# pocketbone.net
KiCad netlist of a schematic drawn in EAGLE
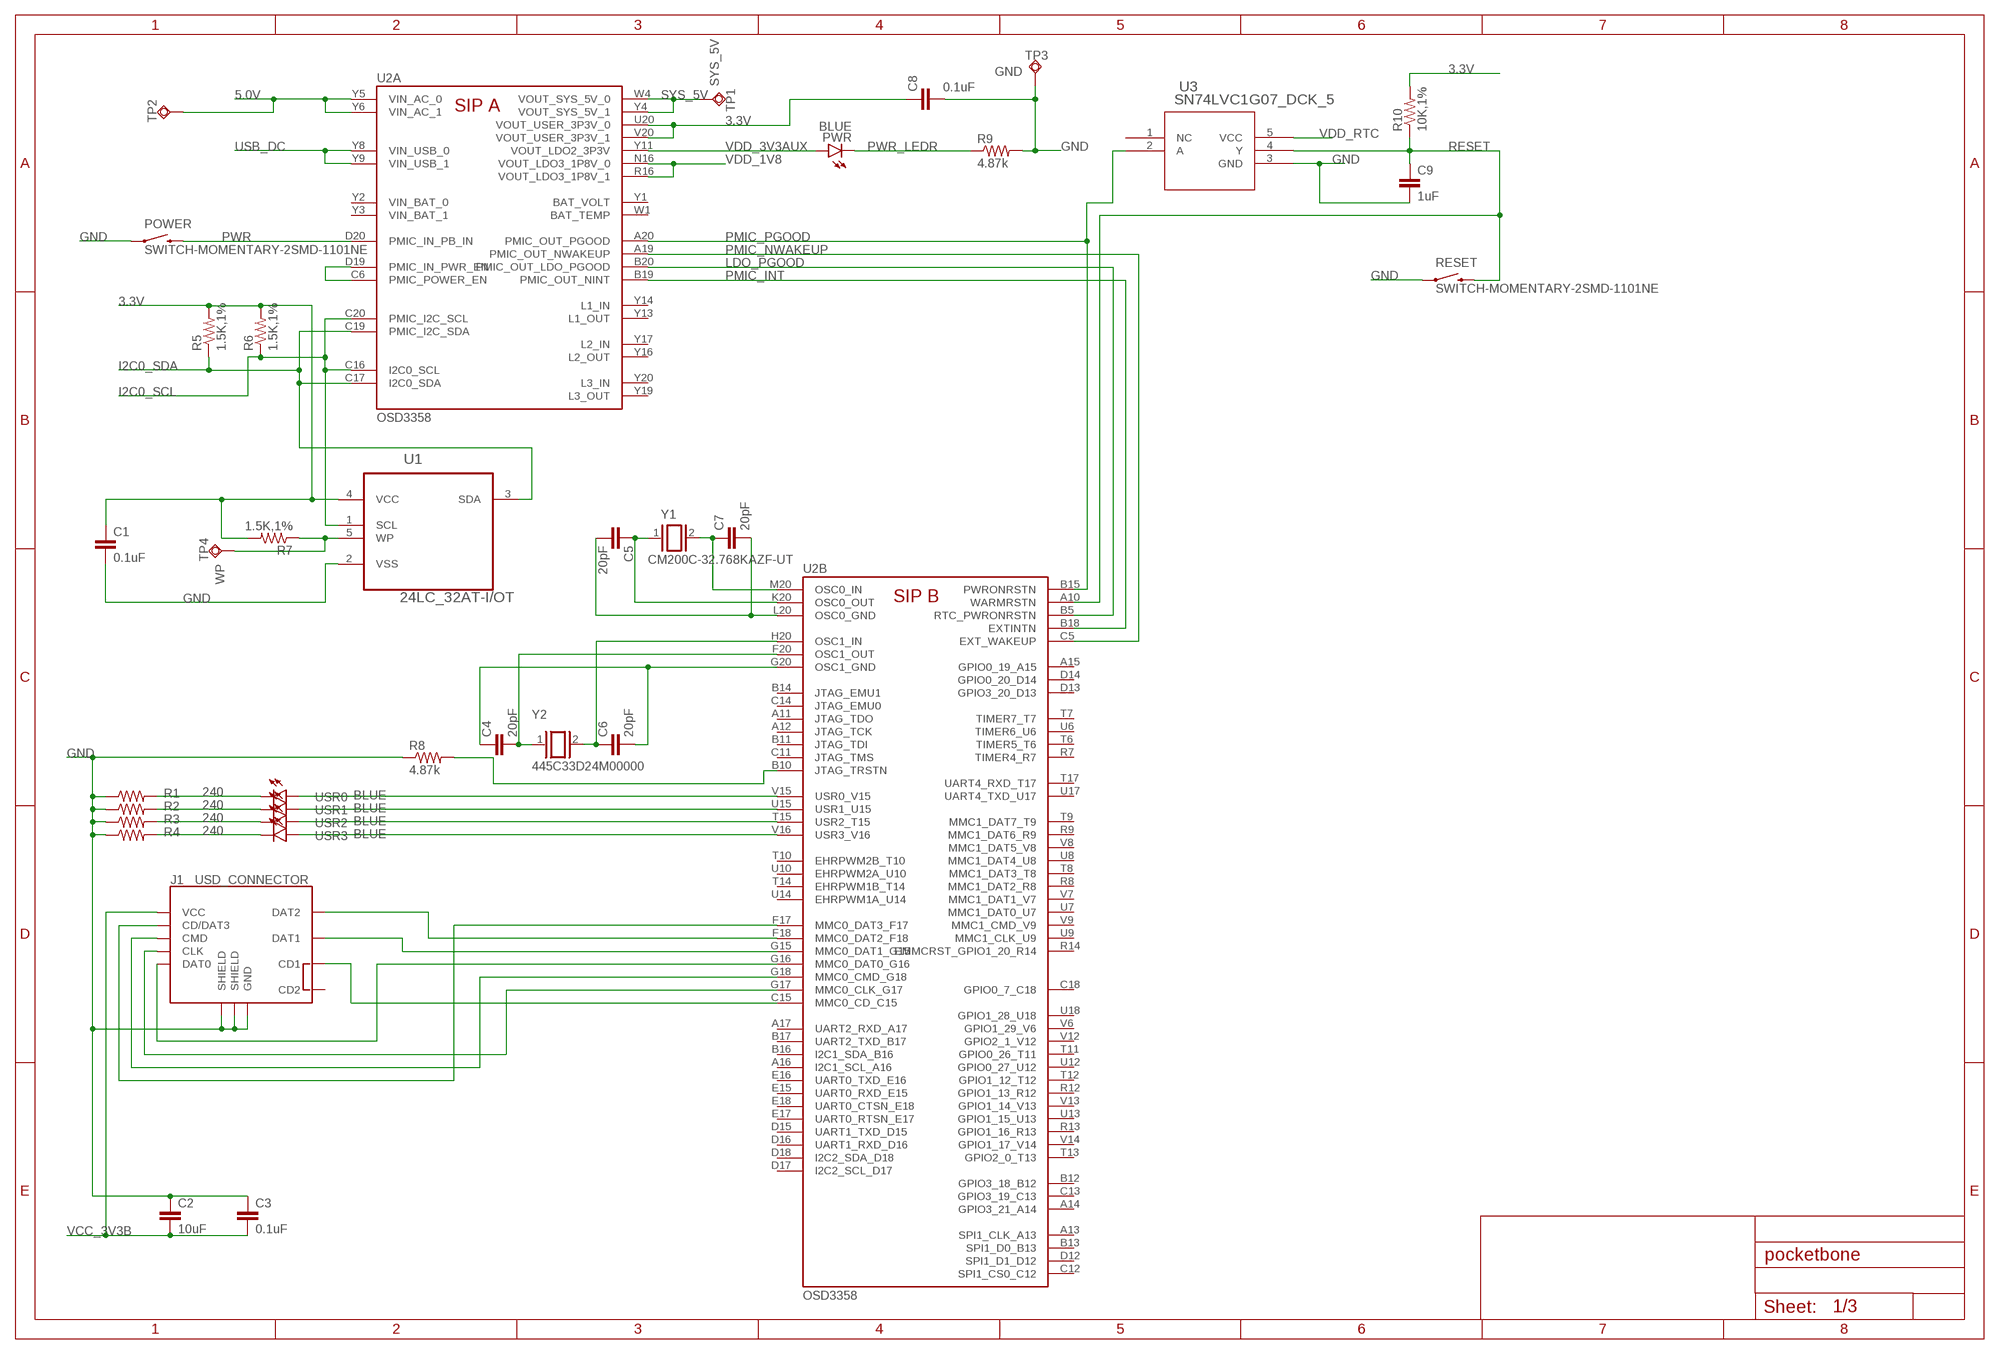
[diagram p0: schematic, sheet 1]
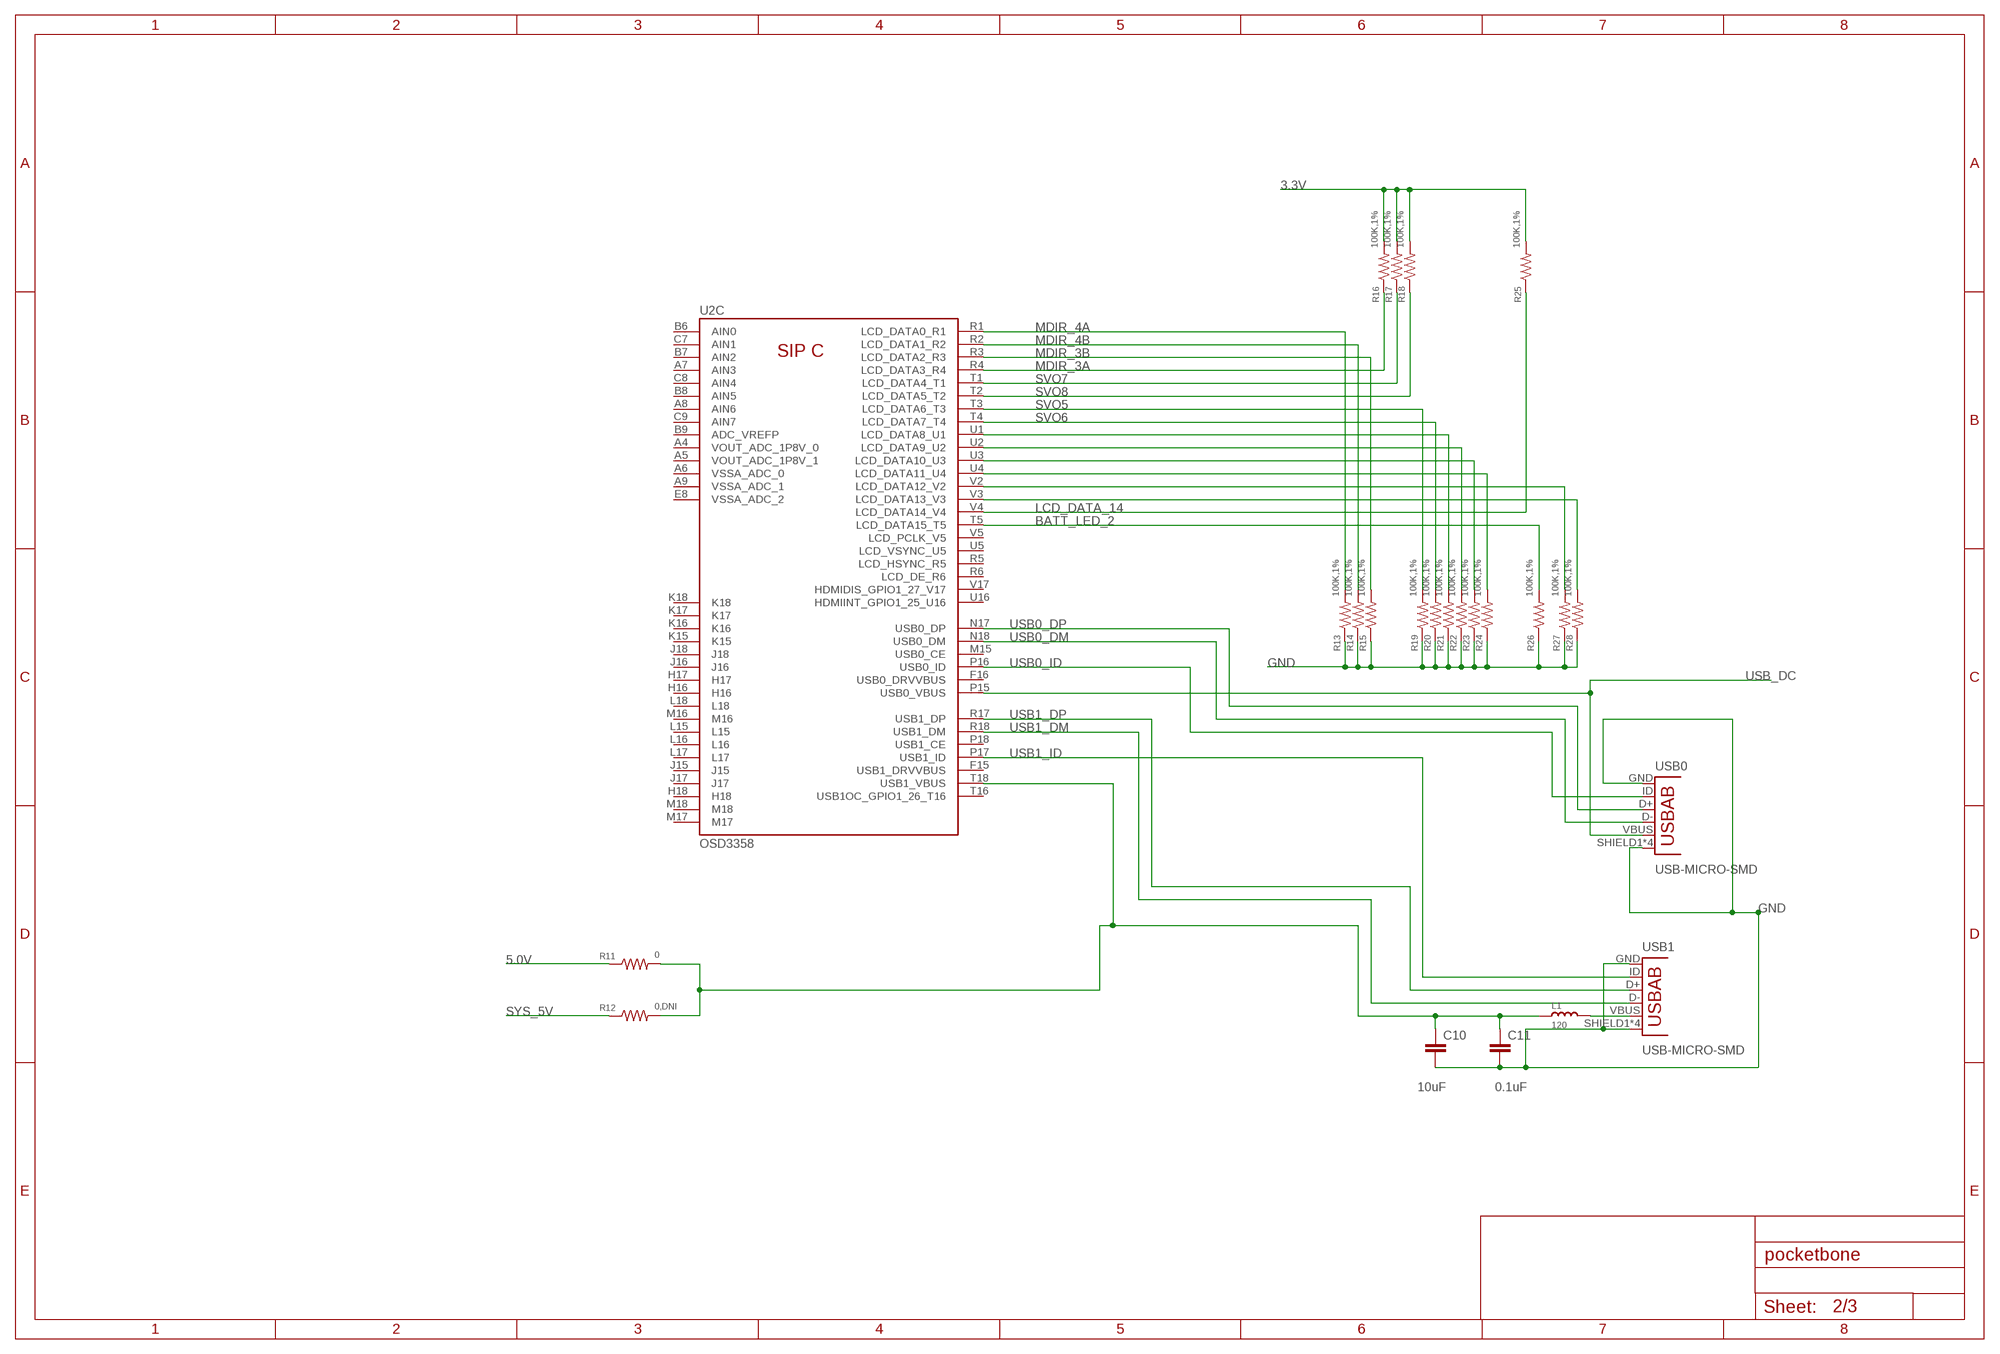
[diagram p1: schematic, sheet 2]
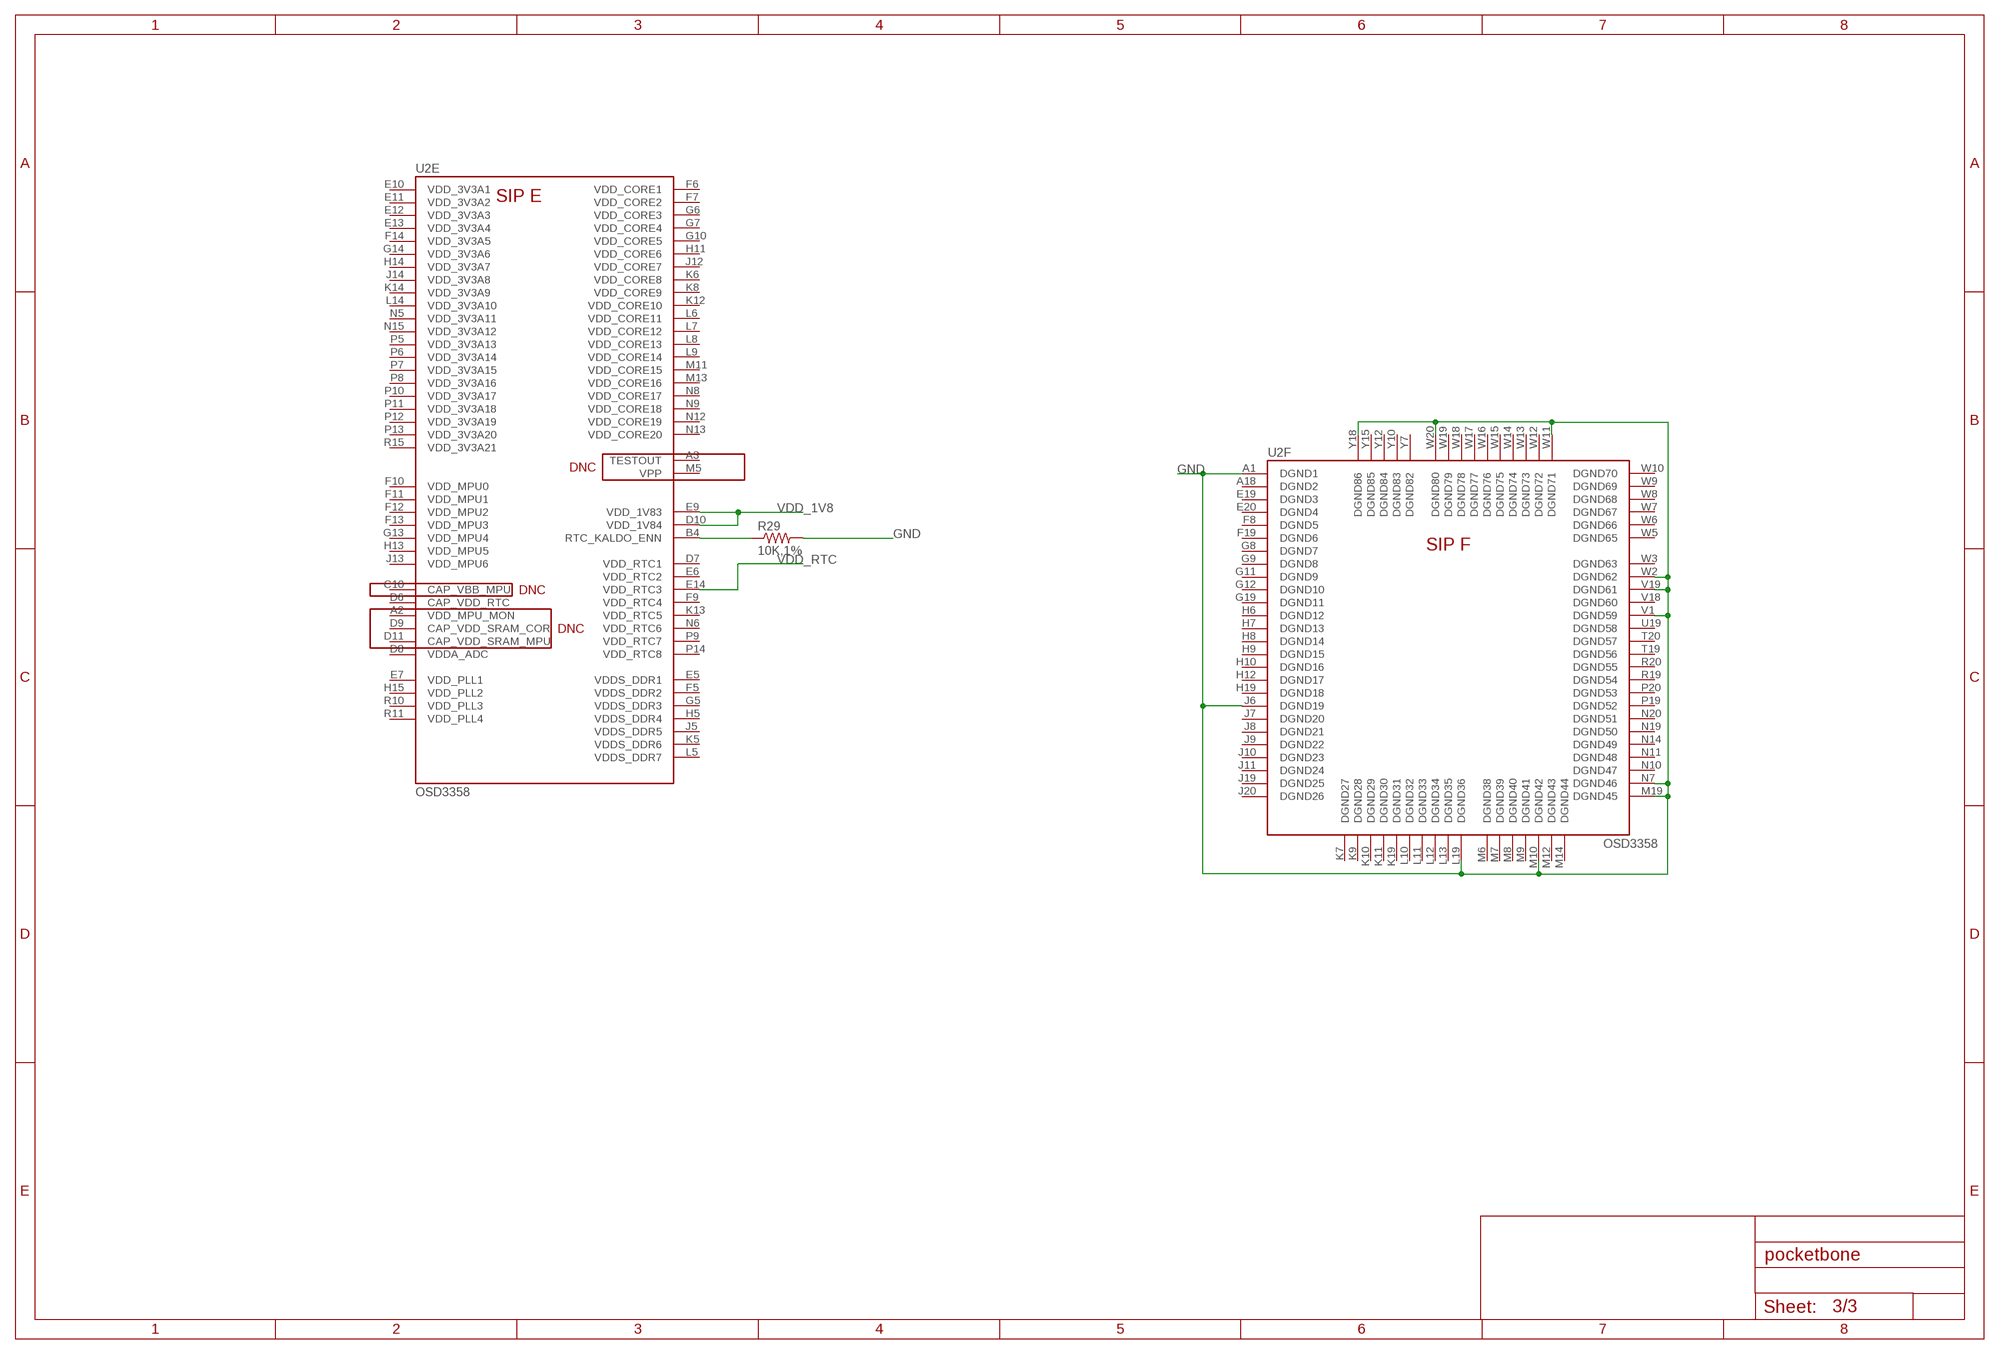
[diagram p2: schematic, sheet 3]

(export (version "E")
  (design (tool "Eeschema 10.0.6"))
  (components
    (comp (ref "C1")
      (value "0.1uF")
      (footprint "eagle-import:0402-CAP")
      (libsource (lib "eagle-import") (part "CAP0402-CAP"))
    )
    (comp (ref "C2")
      (value "10uF")
      (footprint "eagle-import:0805")
      (libsource (lib "eagle-import") (part "CAP0805"))
    )
    (comp (ref "C3")
      (value "0.1uF")
      (footprint "eagle-import:0402-CAP")
      (libsource (lib "eagle-import") (part "CAP0402-CAP"))
    )
    (comp (ref "C4")
      (value "20pF")
      (footprint "eagle-import:0402-CAP")
      (libsource (lib "eagle-import") (part "CAP0402-CAP"))
    )
    (comp (ref "C5")
      (value "20pF")
      (footprint "eagle-import:0402-CAP")
      (libsource (lib "eagle-import") (part "CAP0402-CAP"))
    )
    (comp (ref "C6")
      (value "20pF")
      (footprint "eagle-import:0402-CAP")
      (libsource (lib "eagle-import") (part "CAP0402-CAP"))
    )
    (comp (ref "C7")
      (value "20pF")
      (footprint "eagle-import:0402-CAP")
      (libsource (lib "eagle-import") (part "CAP0402-CAP"))
    )
    (comp (ref "C8")
      (value "0.1uF")
      (footprint "eagle-import:0402-CAP")
      (libsource (lib "eagle-import") (part "CAP0402-CAP"))
    )
    (comp (ref "C9")
      (value "1uF")
      (footprint "eagle-import:0402-CAP")
      (libsource (lib "eagle-import") (part "CAP0402-CAP"))
    )
    (comp (ref "J1")
      (value "USD_CONNECTOR")
      (footprint "eagle-import:MICRO-SD-SOCKET-PP")
      (libsource (lib "eagle-import") (part "USD_CONNECTOR"))
    )
    (comp (ref "POWER")
      (value "SWITCH-MOMENTARY-2SMD-1101NE")
      (footprint "eagle-import:TACTILE-SWITCH-1101NE")
      (libsource (lib "eagle-import") (part "SWITCH-MOMENTARY-2SMD-1101NE"))
    )
    (comp (ref "PWR")
      (value "BLUE")
      (footprint "eagle-import:LED-0603")
      (libsource (lib "eagle-import") (part "LED0603"))
    )
    (comp (ref "R1")
      (value "240")
      (footprint "eagle-import:0402-RES")
      (libsource (lib "eagle-import") (part "RESISTOR0402-RES"))
    )
    (comp (ref "R2")
      (value "240")
      (footprint "eagle-import:0402-RES")
      (libsource (lib "eagle-import") (part "RESISTOR0402-RES"))
    )
    (comp (ref "R3")
      (value "240")
      (footprint "eagle-import:0402-RES")
      (libsource (lib "eagle-import") (part "RESISTOR0402-RES"))
    )
    (comp (ref "R4")
      (value "240")
      (footprint "eagle-import:0402-RES")
      (libsource (lib "eagle-import") (part "RESISTOR0402-RES"))
    )
    (comp (ref "R5")
      (value "1.5K,1%")
      (footprint "eagle-import:0402-RES")
      (libsource (lib "eagle-import") (part "RESISTOR0402-RES"))
    )
    (comp (ref "R6")
      (value "1.5K,1%")
      (footprint "eagle-import:0402-RES")
      (libsource (lib "eagle-import") (part "RESISTOR0402-RES"))
    )
    (comp (ref "R7")
      (value "1.5K,1%")
      (footprint "eagle-import:0402-RES")
      (libsource (lib "eagle-import") (part "RESISTOR0402-RES"))
    )
    (comp (ref "R8")
      (value "4.87k")
      (footprint "eagle-import:0402-RES")
      (libsource (lib "eagle-import") (part "RESISTOR0402-RES"))
    )
    (comp (ref "R9")
      (value "4.87k")
      (footprint "eagle-import:0402-RES")
      (libsource (lib "eagle-import") (part "RESISTOR0402-RES"))
    )
    (comp (ref "R10")
      (value "10K,1%")
      (footprint "eagle-import:0402-RES")
      (libsource (lib "eagle-import") (part "RESISTOR0402-RES"))
    )
    (comp (ref "RESET")
      (value "SWITCH-MOMENTARY-2SMD-1101NE")
      (footprint "eagle-import:TACTILE-SWITCH-1101NE")
      (libsource (lib "eagle-import") (part "SWITCH-MOMENTARY-2SMD-1101NE"))
    )
    (comp (ref "TP1")
      (value "TPSQPAD1-17")
      (footprint "eagle-import:P1-17")
      (fields (field (name "TP_SIGNAL_NAME") "SYS_5V"))
      (libsource (lib "eagle-import") (part "TPSQPAD1-17"))
    )
    (comp (ref "TP2")
      (value "TPSQPAD1-17")
      (footprint "eagle-import:P1-17")
      (fields (field (name "TP_SIGNAL_NAME") "5.0V"))
      (libsource (lib "eagle-import") (part "TPSQPAD1-17"))
    )
    (comp (ref "TP3")
      (value "TPSQPAD1-17")
      (footprint "eagle-import:P1-17")
      (fields (field (name "TP_SIGNAL_NAME") "GND"))
      (libsource (lib "eagle-import") (part "TPSQPAD1-17"))
    )
    (comp (ref "TP4")
      (value "TPSQPAD1-17")
      (footprint "eagle-import:P1-17")
      (fields (field (name "TP_SIGNAL_NAME") "WP"))
      (libsource (lib "eagle-import") (part "TPSQPAD1-17"))
    )
    (comp (ref "U1")
      (value "24LC_32AT-I/OT")
      (footprint "eagle-import:SOT95P290X145-5N")
      (fields (field (name "MPN") "24LC32AT-I/OT"))
      (libsource (lib "eagle-import") (part "24LC_32AT-I/OT"))
    )
    (comp (ref "U2")
      (value "OSD3358")
      (footprint "eagle-import:OSD3358")
      (libsource (lib "eagle-import") (part "OSD3358"))
    )
    (comp (ref "U3")
      (value "SN74LVC1G07_DCK_5")
      (footprint "eagle-import:DCK5")
      (fields
        (field (name "GENERIC_PART_NUMBER") "SN74LVC1G07")
        (field (name "MANUFACTURER") "Texas Instruments")
        (field (name "MANUFACTURER_PART_NUMBER") "sn74lvc1g07_dck_5")
      )
      (libsource (lib "eagle-import") (part "SN74LVC1G07_DCK_5"))
    )
    (comp (ref "USR0")
      (value "BLUE")
      (footprint "eagle-import:LED-0603")
      (libsource (lib "eagle-import") (part "LED0603"))
    )
    (comp (ref "USR1")
      (value "BLUE")
      (footprint "eagle-import:LED-0603")
      (libsource (lib "eagle-import") (part "LED0603"))
    )
    (comp (ref "USR2")
      (value "BLUE")
      (footprint "eagle-import:LED-0603")
      (libsource (lib "eagle-import") (part "LED0603"))
    )
    (comp (ref "USR3")
      (value "BLUE")
      (footprint "eagle-import:LED-0603")
      (libsource (lib "eagle-import") (part "LED0603"))
    )
    (comp (ref "Y1")
      (value "CM200C-32.768KAZF-UT")
      (footprint "eagle-import:CM200C-32.768KAZF-UT")
      (libsource (lib "eagle-import") (part "CM200C-32.768KAZF-UT"))
    )
    (comp (ref "Y2")
      (value "445C33D24M00000")
      (footprint "eagle-import:445C33D24M00000")
      (libsource (lib "eagle-import") (part "445C33D24M00000"))
    )
    (comp (ref "R29")
      (value "10K,1%")
      (footprint "eagle-import:0402-RES")
      (libsource (lib "eagle-import") (part "RESISTOR0402-RES"))
    )
    (comp (ref "C10")
      (value "10uF")
      (footprint "eagle-import:0805")
      (libsource (lib "eagle-import") (part "CAP0805"))
    )
    (comp (ref "C11")
      (value "0.1uF")
      (footprint "eagle-import:0402-CAP")
      (libsource (lib "eagle-import") (part "CAP0402-CAP"))
    )
    (comp (ref "L1")
      (value "120")
      (footprint "eagle-import:L0603")
      (libsource (lib "eagle-import") (part "INDUCTOR/FERRITE-BEAD'0603'"))
    )
    (comp (ref "R11")
      (value "0")
      (footprint "eagle-import:0402-RES")
      (libsource (lib "eagle-import") (part "RESISTOR0402-RES"))
    )
    (comp (ref "R12")
      (value "0,DNI")
      (footprint "eagle-import:0402-RES")
      (libsource (lib "eagle-import") (part "RESISTOR0402-RES"))
    )
    (comp (ref "R13")
      (value "100K,1%")
      (footprint "eagle-import:0402-RES")
      (libsource (lib "eagle-import") (part "RESISTOR0402-RES"))
    )
    (comp (ref "R14")
      (value "100K,1%")
      (footprint "eagle-import:0402-RES")
      (libsource (lib "eagle-import") (part "RESISTOR0402-RES"))
    )
    (comp (ref "R15")
      (value "100K,1%")
      (footprint "eagle-import:0402-RES")
      (libsource (lib "eagle-import") (part "RESISTOR0402-RES"))
    )
    (comp (ref "R16")
      (value "100K,1%")
      (footprint "eagle-import:0402-RES")
      (libsource (lib "eagle-import") (part "RESISTOR0402-RES"))
    )
    (comp (ref "R17")
      (value "100K,1%")
      (footprint "eagle-import:0402-RES")
      (libsource (lib "eagle-import") (part "RESISTOR0402-RES"))
    )
    (comp (ref "R18")
      (value "100K,1%")
      (footprint "eagle-import:0402-RES")
      (libsource (lib "eagle-import") (part "RESISTOR0402-RES"))
    )
    (comp (ref "R19")
      (value "100K,1%")
      (footprint "eagle-import:0402-RES")
      (libsource (lib "eagle-import") (part "RESISTOR0402-RES"))
    )
    (comp (ref "R20")
      (value "100K,1%")
      (footprint "eagle-import:0402-RES")
      (libsource (lib "eagle-import") (part "RESISTOR0402-RES"))
    )
    (comp (ref "R21")
      (value "100K,1%")
      (footprint "eagle-import:0402-RES")
      (libsource (lib "eagle-import") (part "RESISTOR0402-RES"))
    )
    (comp (ref "R22")
      (value "100K,1%")
      (footprint "eagle-import:0402-RES")
      (libsource (lib "eagle-import") (part "RESISTOR0402-RES"))
    )
    (comp (ref "R23")
      (value "100K,1%")
      (footprint "eagle-import:0402-RES")
      (libsource (lib "eagle-import") (part "RESISTOR0402-RES"))
    )
    (comp (ref "R24")
      (value "100K,1%")
      (footprint "eagle-import:0402-RES")
      (libsource (lib "eagle-import") (part "RESISTOR0402-RES"))
    )
    (comp (ref "R25")
      (value "100K,1%")
      (footprint "eagle-import:0402-RES")
      (libsource (lib "eagle-import") (part "RESISTOR0402-RES"))
    )
    (comp (ref "R26")
      (value "100K,1%")
      (footprint "eagle-import:0402-RES")
      (libsource (lib "eagle-import") (part "RESISTOR0402-RES"))
    )
    (comp (ref "R27")
      (value "100K,1%")
      (footprint "eagle-import:0402-RES")
      (libsource (lib "eagle-import") (part "RESISTOR0402-RES"))
    )
    (comp (ref "R28")
      (value "100K,1%")
      (footprint "eagle-import:0402-RES")
      (libsource (lib "eagle-import") (part "RESISTOR0402-RES"))
    )
    (comp (ref "USB0")
      (value "USB-MICRO-SMD")
      (footprint "eagle-import:USB-AB-MICRO-SMD")
      (libsource (lib "eagle-import") (part "USB-AB"))
    )
    (comp (ref "USB1")
      (value "USB-MICRO-SMD")
      (footprint "eagle-import:USB-AB-MICRO-SMD")
      (libsource (lib "eagle-import") (part "USB-AB"))
    )
  )
  (nets
    (net (code "1") (name "3.3V") (class "Default")
      (node (ref "C1") (pin "1") (pinfunction "1_1") (pintype "passive"))
      (node (ref "C8") (pin "1") (pinfunction "1_1") (pintype "passive"))
      (node (ref "R10") (pin "2") (pinfunction "2_2") (pintype "passive"))
      (node (ref "R16") (pin "2") (pinfunction "2_2") (pintype "passive"))
      (node (ref "R17") (pin "2") (pinfunction "2_2") (pintype "passive"))
      (node (ref "R18") (pin "2") (pinfunction "2_2") (pintype "passive"))
      (node (ref "R25") (pin "2") (pinfunction "2_2") (pintype "passive"))
      (node (ref "R5") (pin "2") (pinfunction "2_2") (pintype "passive"))
      (node (ref "R6") (pin "2") (pinfunction "2_2") (pintype "passive"))
      (node (ref "R7") (pin "2") (pinfunction "2_2") (pintype "passive"))
      (node (ref "U1") (pin "4") (pinfunction "VCC_4") (pintype "power_in"))
      (node (ref "U2") (pin "U20") (pinfunction "VOUT_USER_3P3V_0_U20") (pintype "power_in"))
      (node (ref "U2") (pin "V20") (pinfunction "VOUT_USER_3P3V_1_V20") (pintype "power_in"))
    )
    (net (code "2") (name "5.0V") (class "Default")
      (node (ref "R11") (pin "1") (pinfunction "1_1") (pintype "passive"))
      (node (ref "TP2") (pin "TP") (pinfunction "TP_TP") (pintype "input"))
      (node (ref "U2") (pin "Y5") (pinfunction "VIN_AC_0_Y5") (pintype "power_in"))
      (node (ref "U2") (pin "Y6") (pinfunction "VIN_AC_1_Y6") (pintype "power_in"))
    )
    (net (code "3") (name "BATT_LED_2") (class "Default")
      (node (ref "R26") (pin "2") (pinfunction "2_2") (pintype "passive"))
      (node (ref "U2") (pin "T5") (pinfunction "LCD_DATA15_T5_T5") (pintype "bidirectional"))
    )
    (net (code "4") (name "GND") (class "Default")
      (node (ref "C1") (pin "2") (pinfunction "2_2") (pintype "passive"))
      (node (ref "C10") (pin "2") (pinfunction "2_2") (pintype "passive"))
      (node (ref "C11") (pin "2") (pinfunction "2_2") (pintype "passive"))
      (node (ref "C2") (pin "1") (pinfunction "1_1") (pintype "passive"))
      (node (ref "C3") (pin "1") (pinfunction "1_1") (pintype "passive"))
      (node (ref "C8") (pin "2") (pinfunction "2_2") (pintype "passive"))
      (node (ref "C9") (pin "2") (pinfunction "2_2") (pintype "passive"))
      (node (ref "J1") (pin "GND") (pinfunction "GND_GND") (pintype "bidirectional"))
      (node (ref "J1") (pin "GND1") (pinfunction "SHIELD_GND1") (pintype "bidirectional"))
      (node (ref "J1") (pin "GND3") (pinfunction "SHIELD_GND3") (pintype "bidirectional"))
      (node (ref "POWER") (pin "1") (pinfunction "1_1") (pintype "passive"))
      (node (ref "R1") (pin "1") (pinfunction "1_1") (pintype "passive"))
      (node (ref "R13") (pin "1") (pinfunction "1_1") (pintype "passive"))
      (node (ref "R14") (pin "1") (pinfunction "1_1") (pintype "passive"))
      (node (ref "R15") (pin "1") (pinfunction "1_1") (pintype "passive"))
      (node (ref "R19") (pin "1") (pinfunction "1_1") (pintype "passive"))
      (node (ref "R2") (pin "1") (pinfunction "1_1") (pintype "passive"))
      (node (ref "R20") (pin "1") (pinfunction "1_1") (pintype "passive"))
      (node (ref "R21") (pin "1") (pinfunction "1_1") (pintype "passive"))
      (node (ref "R22") (pin "1") (pinfunction "1_1") (pintype "passive"))
      (node (ref "R23") (pin "1") (pinfunction "1_1") (pintype "passive"))
      (node (ref "R24") (pin "1") (pinfunction "1_1") (pintype "passive"))
      (node (ref "R26") (pin "1") (pinfunction "1_1") (pintype "passive"))
      (node (ref "R27") (pin "1") (pinfunction "1_1") (pintype "passive"))
      (node (ref "R28") (pin "1") (pinfunction "1_1") (pintype "passive"))
      (node (ref "R29") (pin "2") (pinfunction "2_2") (pintype "passive"))
      (node (ref "R3") (pin "1") (pinfunction "1_1") (pintype "passive"))
      (node (ref "R4") (pin "1") (pinfunction "1_1") (pintype "passive"))
      (node (ref "R8") (pin "1") (pinfunction "1_1") (pintype "passive"))
      (node (ref "R9") (pin "2") (pinfunction "2_2") (pintype "passive"))
      (node (ref "RESET") (pin "1") (pinfunction "1_1") (pintype "passive"))
      (node (ref "TP3") (pin "TP") (pinfunction "TP_TP") (pintype "input"))
      (node (ref "U1") (pin "2") (pinfunction "VSS_2") (pintype "passive"))
      (node (ref "U2") (pin "A1") (pinfunction "DGND1_A1") (pintype "bidirectional"))
      (node (ref "U2") (pin "J6") (pinfunction "DGND19_J6") (pintype "bidirectional"))
      (node (ref "U2") (pin "L19") (pinfunction "DGND36_L19") (pintype "bidirectional"))
      (node (ref "U2") (pin "M10") (pinfunction "DGND42_M10") (pintype "bidirectional"))
      (node (ref "U2") (pin "M19") (pinfunction "DGND45_M19") (pintype "bidirectional"))
      (node (ref "U2") (pin "N7") (pinfunction "DGND46_N7") (pintype "bidirectional"))
      (node (ref "U2") (pin "V1") (pinfunction "DGND59_V1") (pintype "bidirectional"))
      (node (ref "U2") (pin "V19") (pinfunction "DGND61_V19") (pintype "bidirectional"))
      (node (ref "U2") (pin "W11") (pinfunction "DGND71_W11") (pintype "bidirectional"))
      (node (ref "U2") (pin "W2") (pinfunction "DGND62_W2") (pintype "bidirectional"))
      (node (ref "U2") (pin "W20") (pinfunction "DGND80_W20") (pintype "bidirectional"))
      (node (ref "U2") (pin "Y18") (pinfunction "DGND86_Y18") (pintype "bidirectional"))
      (node (ref "U3") (pin "3") (pinfunction "GND_3") (pintype "power_in"))
      (node (ref "USB0") (pin "GND") (pinfunction "GND_GND") (pintype "bidirectional"))
      (node (ref "USB0") (pin "SHIELD1") (pinfunction "SHIELD_SHIELD1") (pintype "bidirectional"))
      (node (ref "USB0") (pin "SHIELD2") (pinfunction "SHIELD_SHIELD2") (pintype "bidirectional"))
      (node (ref "USB0") (pin "SHIELD3") (pinfunction "SHIELD_SHIELD3") (pintype "bidirectional"))
      (node (ref "USB0") (pin "SHIELD4") (pinfunction "SHIELD_SHIELD4") (pintype "bidirectional"))
      (node (ref "USB1") (pin "GND") (pinfunction "GND_GND") (pintype "bidirectional"))
      (node (ref "USB1") (pin "SHIELD1") (pinfunction "SHIELD_SHIELD1") (pintype "bidirectional"))
      (node (ref "USB1") (pin "SHIELD2") (pinfunction "SHIELD_SHIELD2") (pintype "bidirectional"))
      (node (ref "USB1") (pin "SHIELD3") (pinfunction "SHIELD_SHIELD3") (pintype "bidirectional"))
      (node (ref "USB1") (pin "SHIELD4") (pinfunction "SHIELD_SHIELD4") (pintype "bidirectional"))
    )
    (net (code "5") (name "I2C0_SCL") (class "Default")
      (node (ref "R6") (pin "1") (pinfunction "1_1") (pintype "passive"))
      (node (ref "U1") (pin "1") (pinfunction "SCL_1") (pintype "input"))
      (node (ref "U2") (pin "C16") (pinfunction "I2C0_SCL_C16") (pintype "bidirectional"))
      (node (ref "U2") (pin "C20") (pinfunction "PMIC_I2C_SCL_C20") (pintype "bidirectional"))
    )
    (net (code "6") (name "I2C0_SDA") (class "Default")
      (node (ref "R5") (pin "1") (pinfunction "1_1") (pintype "passive"))
      (node (ref "U1") (pin "3") (pinfunction "SDA_3") (pintype "bidirectional"))
      (node (ref "U2") (pin "C17") (pinfunction "I2C0_SDA_C17") (pintype "bidirectional"))
      (node (ref "U2") (pin "C19") (pinfunction "PMIC_I2C_SDA_C19") (pintype "bidirectional"))
    )
    (net (code "7") (name "LCD_DATA_14") (class "Default")
      (node (ref "R25") (pin "1") (pinfunction "1_1") (pintype "passive"))
      (node (ref "U2") (pin "V4") (pinfunction "LCD_DATA14_V4_V4") (pintype "bidirectional"))
    )
    (net (code "8") (name "LDO_PGOOD") (class "Default")
      (node (ref "U2") (pin "B20") (pinfunction "PMIC_OUT_LDO_PGOOD_B20") (pintype "output"))
      (node (ref "U2") (pin "B5") (pinfunction "RTC_PWRONRSTN_B5") (pintype "bidirectional"))
    )
    (net (code "9") (name "MDIR_3A") (class "Default")
      (node (ref "R16") (pin "1") (pinfunction "1_1") (pintype "passive"))
      (node (ref "U2") (pin "R4") (pinfunction "LCD_DATA3_R4_R4") (pintype "bidirectional"))
    )
    (net (code "10") (name "MDIR_3B") (class "Default")
      (node (ref "R15") (pin "2") (pinfunction "2_2") (pintype "passive"))
      (node (ref "U2") (pin "R3") (pinfunction "LCD_DATA2_R3_R3") (pintype "bidirectional"))
    )
    (net (code "11") (name "MDIR_4A") (class "Default")
      (node (ref "R13") (pin "2") (pinfunction "2_2") (pintype "passive"))
      (node (ref "U2") (pin "R1") (pinfunction "LCD_DATA0_R1_R1") (pintype "bidirectional"))
    )
    (net (code "12") (name "MDIR_4B") (class "Default")
      (node (ref "R14") (pin "2") (pinfunction "2_2") (pintype "passive"))
      (node (ref "U2") (pin "R2") (pinfunction "LCD_DATA1_R2_R2") (pintype "bidirectional"))
    )
    (net (code "13") (name "Net-(L1-Pad2)") (class "Default")
      (node (ref "L1") (pin "2") (pinfunction "2_2") (pintype "passive"))
      (node (ref "USB1") (pin "VBUS") (pinfunction "VBUS_VBUS") (pintype "bidirectional"))
    )
    (net (code "14") (name "Net-(R1-Pad2)") (class "Default")
      (node (ref "R1") (pin "2") (pinfunction "2_2") (pintype "passive"))
      (node (ref "USR0") (pin "C") (pinfunction "C_C") (pintype "passive"))
    )
    (net (code "15") (name "Net-(R2-Pad2)") (class "Default")
      (node (ref "R2") (pin "2") (pinfunction "2_2") (pintype "passive"))
      (node (ref "USR1") (pin "C") (pinfunction "C_C") (pintype "passive"))
    )
    (net (code "16") (name "Net-(R3-Pad2)") (class "Default")
      (node (ref "R3") (pin "2") (pinfunction "2_2") (pintype "passive"))
      (node (ref "USR2") (pin "C") (pinfunction "C_C") (pintype "passive"))
    )
    (net (code "17") (name "Net-(R4-Pad2)") (class "Default")
      (node (ref "R4") (pin "2") (pinfunction "2_2") (pintype "passive"))
      (node (ref "USR3") (pin "C") (pinfunction "C_C") (pintype "passive"))
    )
    (net (code "18") (name "Net-(U1-WP)") (class "Default")
      (node (ref "R7") (pin "1") (pinfunction "1_1") (pintype "passive"))
      (node (ref "TP4") (pin "TP") (pinfunction "TP_TP") (pintype "input"))
      (node (ref "U1") (pin "5") (pinfunction "WP_5") (pintype "input"))
    )
    (net (code "19") (name "Net-(U2A-PMIC_IN_PWR_EN)") (class "Default")
      (node (ref "U2") (pin "C6") (pinfunction "PMIC_POWER_EN_C6") (pintype "output"))
      (node (ref "U2") (pin "D19") (pinfunction "PMIC_IN_PWR_EN_D19") (pintype "input"))
    )
    (net (code "20") (name "Net-(U2B-JTAG_TRSTN)") (class "Default")
      (node (ref "R8") (pin "2") (pinfunction "2_2") (pintype "passive"))
      (node (ref "U2") (pin "B10") (pinfunction "JTAG_TRSTN_B10") (pintype "bidirectional"))
    )
    (net (code "21") (name "Net-(U2B-MMC0_CD_C15)") (class "Default")
      (node (ref "J1") (pin "CD1") (pinfunction "CD1_CD1") (pintype "bidirectional"))
      (node (ref "U2") (pin "C15") (pinfunction "MMC0_CD_C15_C15") (pintype "bidirectional"))
    )
    (net (code "22") (name "Net-(U2B-MMC0_CLK_G17)") (class "Default")
      (node (ref "J1") (pin "CLK") (pinfunction "CLK_CLK") (pintype "bidirectional"))
      (node (ref "U2") (pin "G17") (pinfunction "MMC0_CLK_G17_G17") (pintype "bidirectional"))
    )
    (net (code "23") (name "Net-(U2B-MMC0_CMD_G18)") (class "Default")
      (node (ref "J1") (pin "CMD") (pinfunction "CMD_CMD") (pintype "bidirectional"))
      (node (ref "U2") (pin "G18") (pinfunction "MMC0_CMD_G18_G18") (pintype "bidirectional"))
    )
    (net (code "24") (name "Net-(U2B-MMC0_DAT0_G16)") (class "Default")
      (node (ref "J1") (pin "DAT0") (pinfunction "DAT0_DAT0") (pintype "bidirectional"))
      (node (ref "U2") (pin "G16") (pinfunction "MMC0_DAT0_G16_G16") (pintype "bidirectional"))
    )
    (net (code "25") (name "Net-(U2B-MMC0_DAT1_G15)") (class "Default")
      (node (ref "J1") (pin "DAT1") (pinfunction "DAT1_DAT1") (pintype "bidirectional"))
      (node (ref "U2") (pin "G15") (pinfunction "MMC0_DAT1_G15_G15") (pintype "bidirectional"))
    )
    (net (code "26") (name "Net-(U2B-MMC0_DAT2_F18)") (class "Default")
      (node (ref "J1") (pin "DAT2") (pinfunction "DAT2_DAT2") (pintype "bidirectional"))
      (node (ref "U2") (pin "F18") (pinfunction "MMC0_DAT2_F18_F18") (pintype "bidirectional"))
    )
    (net (code "27") (name "Net-(U2B-MMC0_DAT3_F17)") (class "Default")
      (node (ref "J1") (pin "CD/DAT3") (pinfunction "CD/DAT3_CD/DAT3") (pintype "bidirectional"))
      (node (ref "U2") (pin "F17") (pinfunction "MMC0_DAT3_F17_F17") (pintype "bidirectional"))
    )
    (net (code "28") (name "Net-(U2B-OSC0_GND)") (class "Default")
      (node (ref "C5") (pin "2") (pinfunction "2_2") (pintype "passive"))
      (node (ref "C7") (pin "2") (pinfunction "2_2") (pintype "passive"))
      (node (ref "U2") (pin "L20") (pinfunction "OSC0_GND_L20") (pintype "bidirectional"))
    )
    (net (code "29") (name "Net-(U2B-OSC0_IN)") (class "Default")
      (node (ref "C7") (pin "1") (pinfunction "1_1") (pintype "passive"))
      (node (ref "U2") (pin "M20") (pinfunction "OSC0_IN_M20") (pintype "bidirectional"))
      (node (ref "Y1") (pin "2") (pinfunction "2_2") (pintype "passive"))
    )
    (net (code "30") (name "Net-(U2B-OSC0_OUT)") (class "Default")
      (node (ref "C5") (pin "1") (pinfunction "1_1") (pintype "passive"))
      (node (ref "U2") (pin "K20") (pinfunction "OSC0_OUT_K20") (pintype "bidirectional"))
      (node (ref "Y1") (pin "1") (pinfunction "1_1") (pintype "passive"))
    )
    (net (code "31") (name "Net-(U2B-OSC1_GND)") (class "Default")
      (node (ref "C4") (pin "1") (pinfunction "1_1") (pintype "passive"))
      (node (ref "C6") (pin "2") (pinfunction "2_2") (pintype "passive"))
      (node (ref "U2") (pin "G20") (pinfunction "OSC1_GND_G20") (pintype "bidirectional"))
    )
    (net (code "32") (name "Net-(U2B-OSC1_IN)") (class "Default")
      (node (ref "C6") (pin "1") (pinfunction "1_1") (pintype "passive"))
      (node (ref "U2") (pin "H20") (pinfunction "OSC1_IN_H20") (pintype "bidirectional"))
      (node (ref "Y2") (pin "2") (pinfunction "2_2") (pintype "passive"))
    )
    (net (code "33") (name "Net-(U2B-OSC1_OUT)") (class "Default")
      (node (ref "C4") (pin "2") (pinfunction "2_2") (pintype "passive"))
      (node (ref "U2") (pin "F20") (pinfunction "OSC1_OUT_F20") (pintype "bidirectional"))
      (node (ref "Y2") (pin "1") (pinfunction "1_1") (pintype "passive"))
    )
    (net (code "34") (name "Net-(U2B-USR0_V15)") (class "Default")
      (node (ref "U2") (pin "V15") (pinfunction "USR0_V15_V15") (pintype "bidirectional"))
      (node (ref "USR0") (pin "A") (pinfunction "A_A") (pintype "passive"))
    )
    (net (code "35") (name "Net-(U2B-USR1_U15)") (class "Default")
      (node (ref "U2") (pin "U15") (pinfunction "USR1_U15_U15") (pintype "bidirectional"))
      (node (ref "USR1") (pin "A") (pinfunction "A_A") (pintype "passive"))
    )
    (net (code "36") (name "Net-(U2B-USR2_T15)") (class "Default")
      (node (ref "U2") (pin "T15") (pinfunction "USR2_T15_T15") (pintype "bidirectional"))
      (node (ref "USR2") (pin "A") (pinfunction "A_A") (pintype "passive"))
    )
    (net (code "37") (name "Net-(U2B-USR3_V16)") (class "Default")
      (node (ref "U2") (pin "V16") (pinfunction "USR3_V16_V16") (pintype "bidirectional"))
      (node (ref "USR3") (pin "A") (pinfunction "A_A") (pintype "passive"))
    )
    (net (code "38") (name "Net-(U2C-LCD_DATA8_U1)") (class "Default")
      (node (ref "R21") (pin "2") (pinfunction "2_2") (pintype "passive"))
      (node (ref "U2") (pin "U1") (pinfunction "LCD_DATA8_U1_U1") (pintype "bidirectional"))
    )
    (net (code "39") (name "Net-(U2C-LCD_DATA9_U2)") (class "Default")
      (node (ref "R22") (pin "2") (pinfunction "2_2") (pintype "passive"))
      (node (ref "U2") (pin "U2") (pinfunction "LCD_DATA9_U2_U2") (pintype "bidirectional"))
    )
    (net (code "40") (name "Net-(U2C-LCD_DATA10_U3)") (class "Default")
      (node (ref "R23") (pin "2") (pinfunction "2_2") (pintype "passive"))
      (node (ref "U2") (pin "U3") (pinfunction "LCD_DATA10_U3_U3") (pintype "bidirectional"))
    )
    (net (code "41") (name "Net-(U2C-LCD_DATA11_U4)") (class "Default")
      (node (ref "R24") (pin "2") (pinfunction "2_2") (pintype "passive"))
      (node (ref "U2") (pin "U4") (pinfunction "LCD_DATA11_U4_U4") (pintype "bidirectional"))
    )
    (net (code "42") (name "Net-(U2C-LCD_DATA12_V2)") (class "Default")
      (node (ref "R27") (pin "2") (pinfunction "2_2") (pintype "passive"))
      (node (ref "U2") (pin "V2") (pinfunction "LCD_DATA12_V2_V2") (pintype "bidirectional"))
    )
    (net (code "43") (name "Net-(U2C-LCD_DATA13_V3)") (class "Default")
      (node (ref "R28") (pin "2") (pinfunction "2_2") (pintype "passive"))
      (node (ref "U2") (pin "V3") (pinfunction "LCD_DATA13_V3_V3") (pintype "bidirectional"))
    )
    (net (code "44") (name "Net-(U2C-USB1_VBUS)") (class "Default")
      (node (ref "C10") (pin "1") (pinfunction "1_1") (pintype "passive"))
      (node (ref "C11") (pin "1") (pinfunction "1_1") (pintype "passive"))
      (node (ref "L1") (pin "1") (pinfunction "1_1") (pintype "passive"))
      (node (ref "R11") (pin "2") (pinfunction "2_2") (pintype "passive"))
      (node (ref "R12") (pin "2") (pinfunction "2_2") (pintype "passive"))
      (node (ref "U2") (pin "T18") (pinfunction "USB1_VBUS_T18") (pintype "bidirectional"))
    )
    (net (code "45") (name "Net-(U2E-RTC_KALDO_ENN)") (class "Default")
      (node (ref "R29") (pin "1") (pinfunction "1_1") (pintype "passive"))
      (node (ref "U2") (pin "B4") (pinfunction "RTC_KALDO_ENN_B4") (pintype "bidirectional"))
    )
    (net (code "46") (name "PMIC_INT") (class "Default")
      (node (ref "U2") (pin "B18") (pinfunction "EXTINTN_B18") (pintype "bidirectional"))
      (node (ref "U2") (pin "B19") (pinfunction "PMIC_OUT_NINT_B19") (pintype "output"))
    )
    (net (code "47") (name "PMIC_NWAKEUP") (class "Default")
      (node (ref "U2") (pin "A19") (pinfunction "PMIC_OUT_NWAKEUP_A19") (pintype "output"))
      (node (ref "U2") (pin "C5") (pinfunction "EXT_WAKEUP_C5") (pintype "bidirectional"))
    )
    (net (code "48") (name "PMIC_PGOOD") (class "Default")
      (node (ref "U2") (pin "A20") (pinfunction "PMIC_OUT_PGOOD_A20") (pintype "output"))
      (node (ref "U2") (pin "B15") (pinfunction "PWRONRSTN_B15") (pintype "bidirectional"))
      (node (ref "U3") (pin "2") (pinfunction "A_2") (pintype "input"))
    )
    (net (code "49") (name "PWR") (class "Default")
      (node (ref "POWER") (pin "2") (pinfunction "2_2") (pintype "passive"))
      (node (ref "U2") (pin "D20") (pinfunction "PMIC_IN_PB_IN_D20") (pintype "bidirectional"))
    )
    (net (code "50") (name "PWR_LEDR") (class "Default")
      (node (ref "PWR") (pin "C") (pinfunction "C_C") (pintype "passive"))
      (node (ref "R9") (pin "1") (pinfunction "1_1") (pintype "passive"))
    )
    (net (code "51") (name "RESET") (class "Default")
      (node (ref "C9") (pin "1") (pinfunction "1_1") (pintype "passive"))
      (node (ref "R10") (pin "1") (pinfunction "1_1") (pintype "passive"))
      (node (ref "RESET") (pin "2") (pinfunction "2_2") (pintype "passive"))
      (node (ref "U2") (pin "A10") (pinfunction "WARMRSTN_A10") (pintype "bidirectional"))
      (node (ref "U3") (pin "4") (pinfunction "Y_4") (pintype "output"))
    )
    (net (code "52") (name "SVO5") (class "Default")
      (node (ref "R19") (pin "2") (pinfunction "2_2") (pintype "passive"))
      (node (ref "U2") (pin "T3") (pinfunction "LCD_DATA6_T3_T3") (pintype "bidirectional"))
    )
    (net (code "53") (name "SVO6") (class "Default")
      (node (ref "R20") (pin "2") (pinfunction "2_2") (pintype "passive"))
      (node (ref "U2") (pin "T4") (pinfunction "LCD_DATA7_T4_T4") (pintype "bidirectional"))
    )
    (net (code "54") (name "SVO7") (class "Default")
      (node (ref "R17") (pin "1") (pinfunction "1_1") (pintype "passive"))
      (node (ref "U2") (pin "T1") (pinfunction "LCD_DATA4_T1_T1") (pintype "bidirectional"))
    )
    (net (code "55") (name "SVO8") (class "Default")
      (node (ref "R18") (pin "1") (pinfunction "1_1") (pintype "passive"))
      (node (ref "U2") (pin "T2") (pinfunction "LCD_DATA5_T2_T2") (pintype "bidirectional"))
    )
    (net (code "56") (name "SYS_5V") (class "Default")
      (node (ref "R12") (pin "1") (pinfunction "1_1") (pintype "passive"))
      (node (ref "TP1") (pin "TP") (pinfunction "TP_TP") (pintype "input"))
      (node (ref "U2") (pin "W4") (pinfunction "VOUT_SYS_5V_0_W4") (pintype "power_in"))
      (node (ref "U2") (pin "Y4") (pinfunction "VOUT_SYS_5V_1_Y4") (pintype "power_in"))
    )
    (net (code "57") (name "USB0_DM") (class "Default")
      (node (ref "U2") (pin "N18") (pinfunction "USB0_DM_N18") (pintype "bidirectional"))
      (node (ref "USB0") (pin "D-") (pinfunction "D-_D-") (pintype "bidirectional"))
    )
    (net (code "58") (name "USB0_DP") (class "Default")
      (node (ref "U2") (pin "N17") (pinfunction "USB0_DP_N17") (pintype "bidirectional"))
      (node (ref "USB0") (pin "D+") (pinfunction "D+_D+") (pintype "bidirectional"))
    )
    (net (code "59") (name "USB0_ID") (class "Default")
      (node (ref "U2") (pin "P16") (pinfunction "USB0_ID_P16") (pintype "bidirectional"))
      (node (ref "USB0") (pin "ID") (pinfunction "USBID_ID") (pintype "bidirectional"))
    )
    (net (code "60") (name "USB1_DM") (class "Default")
      (node (ref "U2") (pin "R18") (pinfunction "USB1_DM_R18") (pintype "bidirectional"))
      (node (ref "USB1") (pin "D-") (pinfunction "D-_D-") (pintype "bidirectional"))
    )
    (net (code "61") (name "USB1_DP") (class "Default")
      (node (ref "U2") (pin "R17") (pinfunction "USB1_DP_R17") (pintype "bidirectional"))
      (node (ref "USB1") (pin "D+") (pinfunction "D+_D+") (pintype "bidirectional"))
    )
    (net (code "62") (name "USB1_ID") (class "Default")
      (node (ref "U2") (pin "P17") (pinfunction "USB1_ID_P17") (pintype "bidirectional"))
      (node (ref "USB1") (pin "ID") (pinfunction "USBID_ID") (pintype "bidirectional"))
    )
    (net (code "63") (name "USB_DC") (class "Default")
      (node (ref "U2") (pin "P15") (pinfunction "USB0_VBUS_P15") (pintype "bidirectional"))
      (node (ref "U2") (pin "Y8") (pinfunction "VIN_USB_0_Y8") (pintype "power_in"))
      (node (ref "U2") (pin "Y9") (pinfunction "VIN_USB_1_Y9") (pintype "power_in"))
      (node (ref "USB0") (pin "VBUS") (pinfunction "VBUS_VBUS") (pintype "bidirectional"))
    )
    (net (code "64") (name "VCC_3V3B") (class "Default")
      (node (ref "C2") (pin "2") (pinfunction "2_2") (pintype "passive"))
      (node (ref "C3") (pin "2") (pinfunction "2_2") (pintype "passive"))
      (node (ref "J1") (pin "VCC") (pinfunction "VCC_VCC") (pintype "bidirectional"))
    )
    (net (code "65") (name "VDD_1V8") (class "Default")
      (node (ref "U2") (pin "D10") (pinfunction "VDD_1V84_D10") (pintype "bidirectional"))
      (node (ref "U2") (pin "E9") (pinfunction "VDD_1V83_E9") (pintype "bidirectional"))
      (node (ref "U2") (pin "N16") (pinfunction "VOUT_LDO3_1P8V_0_N16") (pintype "power_in"))
      (node (ref "U2") (pin "R16") (pinfunction "VOUT_LDO3_1P8V_1_R16") (pintype "power_in"))
    )
    (net (code "66") (name "VDD_3V3AUX") (class "Default")
      (node (ref "PWR") (pin "A") (pinfunction "A_A") (pintype "passive"))
      (node (ref "U2") (pin "Y11") (pinfunction "VOUT_LDO2_3P3V_Y11") (pintype "power_in"))
    )
    (net (code "67") (name "VDD_RTC") (class "Default")
      (node (ref "U2") (pin "E14") (pinfunction "VDD_RTC3_E14") (pintype "bidirectional"))
      (node (ref "U3") (pin "5") (pinfunction "VCC_5") (pintype "power_in"))
    )
    (net (code "68") (name "VIN_BAT_0") (class "Default")
      (node (ref "U2") (pin "Y2") (pinfunction "VIN_BAT_0_Y2") (pintype "power_in"))
    )
    (net (code "69") (name "VIN_BAT_1") (class "Default")
      (node (ref "U2") (pin "Y3") (pinfunction "VIN_BAT_1_Y3") (pintype "power_in"))
    )
    (net (code "70") (name "unconnected-(J1-PadCD2)") (class "Default")
      (node (ref "J1") (pin "CD2") (pinfunction "CD2_CD2") (pintype "bidirectional"))
    )
    (net (code "71") (name "unconnected-(U2-PadH16)") (class "Default")
      (node (ref "U2") (pin "H16") (pinfunction "H16_H16") (pintype "bidirectional"))
    )
    (net (code "72") (name "unconnected-(U2-PadH17)") (class "Default")
      (node (ref "U2") (pin "H17") (pinfunction "H17_H17") (pintype "bidirectional"))
    )
    (net (code "73") (name "unconnected-(U2-PadH18)") (class "Default")
      (node (ref "U2") (pin "H18") (pinfunction "H18_H18") (pintype "bidirectional"))
    )
    (net (code "74") (name "unconnected-(U2-PadJ15)") (class "Default")
      (node (ref "U2") (pin "J15") (pinfunction "J15_J15") (pintype "bidirectional"))
    )
    (net (code "75") (name "unconnected-(U2-PadJ16)") (class "Default")
      (node (ref "U2") (pin "J16") (pinfunction "J16_J16") (pintype "bidirectional"))
    )
    (net (code "76") (name "unconnected-(U2-PadJ17)") (class "Default")
      (node (ref "U2") (pin "J17") (pinfunction "J17_J17") (pintype "bidirectional"))
    )
    (net (code "77") (name "unconnected-(U2-PadJ18)") (class "Default")
      (node (ref "U2") (pin "J18") (pinfunction "J18_J18") (pintype "bidirectional"))
    )
    (net (code "78") (name "unconnected-(U2-PadK15)") (class "Default")
      (node (ref "U2") (pin "K15") (pinfunction "K15_K15") (pintype "bidirectional"))
    )
    (net (code "79") (name "unconnected-(U2-PadK16)") (class "Default")
      (node (ref "U2") (pin "K16") (pinfunction "K16_K16") (pintype "bidirectional"))
    )
    (net (code "80") (name "unconnected-(U2-PadK17)") (class "Default")
      (node (ref "U2") (pin "K17") (pinfunction "K17_K17") (pintype "bidirectional"))
    )
    (net (code "81") (name "unconnected-(U2-PadK18)") (class "Default")
      (node (ref "U2") (pin "K18") (pinfunction "K18_K18") (pintype "bidirectional"))
    )
    (net (code "82") (name "unconnected-(U2-PadL15)") (class "Default")
      (node (ref "U2") (pin "L15") (pinfunction "L15_L15") (pintype "bidirectional"))
    )
    (net (code "83") (name "unconnected-(U2-PadL16)") (class "Default")
      (node (ref "U2") (pin "L16") (pinfunction "L16_L16") (pintype "bidirectional"))
    )
    (net (code "84") (name "unconnected-(U2-PadL17)") (class "Default")
      (node (ref "U2") (pin "L17") (pinfunction "L17_L17") (pintype "bidirectional"))
    )
    (net (code "85") (name "unconnected-(U2-PadL18)") (class "Default")
      (node (ref "U2") (pin "L18") (pinfunction "L18_L18") (pintype "bidirectional"))
    )
    (net (code "86") (name "unconnected-(U2-PadM16)") (class "Default")
      (node (ref "U2") (pin "M16") (pinfunction "M16_M16") (pintype "bidirectional"))
    )
    (net (code "87") (name "unconnected-(U2-PadM17)") (class "Default")
      (node (ref "U2") (pin "M17") (pinfunction "M17_M17") (pintype "bidirectional"))
    )
    (net (code "88") (name "unconnected-(U2-PadM18)") (class "Default")
      (node (ref "U2") (pin "M18") (pinfunction "M18_M18") (pintype "bidirectional"))
    )
    (net (code "89") (name "unconnected-(U2A-BAT_TEMP-PadW1)") (class "Default")
      (node (ref "U2") (pin "W1") (pinfunction "BAT_TEMP_W1") (pintype "bidirectional"))
    )
    (net (code "90") (name "unconnected-(U2A-BAT_VOLT-PadY1)") (class "Default")
      (node (ref "U2") (pin "Y1") (pinfunction "BAT_VOLT_Y1") (pintype "bidirectional"))
    )
    (net (code "91") (name "unconnected-(U2A-L1_IN-PadY14)") (class "Default")
      (node (ref "U2") (pin "Y14") (pinfunction "L1_IN_Y14") (pintype "bidirectional"))
    )
    (net (code "92") (name "unconnected-(U2A-L1_OUT-PadY13)") (class "Default")
      (node (ref "U2") (pin "Y13") (pinfunction "L1_OUT_Y13") (pintype "bidirectional"))
    )
    (net (code "93") (name "unconnected-(U2A-L2_IN-PadY17)") (class "Default")
      (node (ref "U2") (pin "Y17") (pinfunction "L2_IN_Y17") (pintype "bidirectional"))
    )
    (net (code "94") (name "unconnected-(U2A-L2_OUT-PadY16)") (class "Default")
      (node (ref "U2") (pin "Y16") (pinfunction "L2_OUT_Y16") (pintype "bidirectional"))
    )
    (net (code "95") (name "unconnected-(U2A-L3_IN-PadY20)") (class "Default")
      (node (ref "U2") (pin "Y20") (pinfunction "L3_IN_Y20") (pintype "bidirectional"))
    )
    (net (code "96") (name "unconnected-(U2A-L3_OUT-PadY19)") (class "Default")
      (node (ref "U2") (pin "Y19") (pinfunction "L3_OUT_Y19") (pintype "bidirectional"))
    )
    (net (code "97") (name "unconnected-(U2B-EHRPWM1A_U14-PadU14)") (class "Default")
      (node (ref "U2") (pin "U14") (pinfunction "EHRPWM1A_U14_U14") (pintype "bidirectional"))
    )
    (net (code "98") (name "unconnected-(U2B-EHRPWM1B_T14-PadT14)") (class "Default")
      (node (ref "U2") (pin "T14") (pinfunction "EHRPWM1B_T14_T14") (pintype "bidirectional"))
    )
    (net (code "99") (name "unconnected-(U2B-EHRPWM2A_U10-PadU10)") (class "Default")
      (node (ref "U2") (pin "U10") (pinfunction "EHRPWM2A_U10_U10") (pintype "bidirectional"))
    )
    (net (code "100") (name "unconnected-(U2B-EHRPWM2B_T10-PadT10)") (class "Default")
      (node (ref "U2") (pin "T10") (pinfunction "EHRPWM2B_T10_T10") (pintype "bidirectional"))
    )
    (net (code "101") (name "unconnected-(U2B-EMMCRST_GPIO1_20_R14-PadR14)") (class "Default")
      (node (ref "U2") (pin "R14") (pinfunction "EMMCRST_GPIO1_20_R14_R14") (pintype "bidirectional"))
    )
    (net (code "102") (name "unconnected-(U2B-GPIO0_7_C18-PadC18)") (class "Default")
      (node (ref "U2") (pin "C18") (pinfunction "GPIO0_7_C18_C18") (pintype "bidirectional"))
    )
    (net (code "103") (name "unconnected-(U2B-GPIO0_19_A15-PadA15)") (class "Default")
      (node (ref "U2") (pin "A15") (pinfunction "GPIO0_19_A15_A15") (pintype "bidirectional"))
    )
    (net (code "104") (name "unconnected-(U2B-GPIO0_20_D14-PadD14)") (class "Default")
      (node (ref "U2") (pin "D14") (pinfunction "GPIO0_20_D14_D14") (pintype "bidirectional"))
    )
    (net (code "105") (name "unconnected-(U2B-GPIO0_26_T11-PadT11)") (class "Default")
      (node (ref "U2") (pin "T11") (pinfunction "GPIO0_26_T11_T11") (pintype "bidirectional"))
    )
    (net (code "106") (name "unconnected-(U2B-GPIO0_27_U12-PadU12)") (class "Default")
      (node (ref "U2") (pin "U12") (pinfunction "GPIO0_27_U12_U12") (pintype "bidirectional"))
    )
    (net (code "107") (name "unconnected-(U2B-GPIO1_12_T12-PadT12)") (class "Default")
      (node (ref "U2") (pin "T12") (pinfunction "GPIO1_12_T12_T12") (pintype "bidirectional"))
    )
    (net (code "108") (name "unconnected-(U2B-GPIO1_13_R12-PadR12)") (class "Default")
      (node (ref "U2") (pin "R12") (pinfunction "GPIO1_13_R12_R12") (pintype "bidirectional"))
    )
    (net (code "109") (name "unconnected-(U2B-GPIO1_14_V13-PadV13)") (class "Default")
      (node (ref "U2") (pin "V13") (pinfunction "GPIO1_14_V13_V13") (pintype "bidirectional"))
    )
    (net (code "110") (name "unconnected-(U2B-GPIO1_15_U13-PadU13)") (class "Default")
      (node (ref "U2") (pin "U13") (pinfunction "GPIO1_15_U13_U13") (pintype "bidirectional"))
    )
    (net (code "111") (name "unconnected-(U2B-GPIO1_16_R13-PadR13)") (class "Default")
      (node (ref "U2") (pin "R13") (pinfunction "GPIO1_16_R13_R13") (pintype "bidirectional"))
    )
    (net (code "112") (name "unconnected-(U2B-GPIO1_17_V14-PadV14)") (class "Default")
      (node (ref "U2") (pin "V14") (pinfunction "GPIO1_17_V14_V14") (pintype "bidirectional"))
    )
    (net (code "113") (name "unconnected-(U2B-GPIO1_28_U18-PadU18)") (class "Default")
      (node (ref "U2") (pin "U18") (pinfunction "GPIO1_28_U18_U18") (pintype "bidirectional"))
    )
    (net (code "114") (name "unconnected-(U2B-GPIO1_29_V6-PadV6)") (class "Default")
      (node (ref "U2") (pin "V6") (pinfunction "GPIO1_29_V6_V6") (pintype "bidirectional"))
    )
    (net (code "115") (name "unconnected-(U2B-GPIO2_0_T13-PadT13)") (class "Default")
      (node (ref "U2") (pin "T13") (pinfunction "GPIO2_0_T13_T13") (pintype "bidirectional"))
    )
    (net (code "116") (name "unconnected-(U2B-GPIO2_1_V12-PadV12)") (class "Default")
      (node (ref "U2") (pin "V12") (pinfunction "GPIO2_1_V12_V12") (pintype "bidirectional"))
    )
    (net (code "117") (name "unconnected-(U2B-GPIO3_18_B12-PadB12)") (class "Default")
      (node (ref "U2") (pin "B12") (pinfunction "GPIO3_18_B12_B12") (pintype "bidirectional"))
    )
    (net (code "118") (name "unconnected-(U2B-GPIO3_19_C13-PadC13)") (class "Default")
      (node (ref "U2") (pin "C13") (pinfunction "GPIO3_19_C13_C13") (pintype "bidirectional"))
    )
    (net (code "119") (name "unconnected-(U2B-GPIO3_20_D13-PadD13)") (class "Default")
      (node (ref "U2") (pin "D13") (pinfunction "GPIO3_20_D13_D13") (pintype "bidirectional"))
    )
    (net (code "120") (name "unconnected-(U2B-GPIO3_21_A14-PadA14)") (class "Default")
      (node (ref "U2") (pin "A14") (pinfunction "GPIO3_21_A14_A14") (pintype "bidirectional"))
    )
    (net (code "121") (name "unconnected-(U2B-I2C1_SCL_A16-PadA16)") (class "Default")
      (node (ref "U2") (pin "A16") (pinfunction "I2C1_SCL_A16_A16") (pintype "bidirectional"))
    )
    (net (code "122") (name "unconnected-(U2B-I2C1_SDA_B16-PadB16)") (class "Default")
      (node (ref "U2") (pin "B16") (pinfunction "I2C1_SDA_B16_B16") (pintype "bidirectional"))
    )
    (net (code "123") (name "unconnected-(U2B-I2C2_SCL_D17-PadD17)") (class "Default")
      (node (ref "U2") (pin "D17") (pinfunction "I2C2_SCL_D17_D17") (pintype "bidirectional"))
    )
    (net (code "124") (name "unconnected-(U2B-I2C2_SDA_D18-PadD18)") (class "Default")
      (node (ref "U2") (pin "D18") (pinfunction "I2C2_SDA_D18_D18") (pintype "bidirectional"))
    )
    (net (code "125") (name "unconnected-(U2B-JTAG_EMU0-PadC14)") (class "Default")
      (node (ref "U2") (pin "C14") (pinfunction "JTAG_EMU0_C14") (pintype "bidirectional"))
    )
    (net (code "126") (name "unconnected-(U2B-JTAG_EMU1-PadB14)") (class "Default")
      (node (ref "U2") (pin "B14") (pinfunction "JTAG_EMU1_B14") (pintype "bidirectional"))
    )
    (net (code "127") (name "unconnected-(U2B-JTAG_TCK-PadA12)") (class "Default")
      (node (ref "U2") (pin "A12") (pinfunction "JTAG_TCK_A12") (pintype "bidirectional"))
    )
    (net (code "128") (name "unconnected-(U2B-JTAG_TDI-PadB11)") (class "Default")
      (node (ref "U2") (pin "B11") (pinfunction "JTAG_TDI_B11") (pintype "bidirectional"))
    )
    (net (code "129") (name "unconnected-(U2B-JTAG_TDO-PadA11)") (class "Default")
      (node (ref "U2") (pin "A11") (pinfunction "JTAG_TDO_A11") (pintype "bidirectional"))
    )
    (net (code "130") (name "unconnected-(U2B-JTAG_TMS-PadC11)") (class "Default")
      (node (ref "U2") (pin "C11") (pinfunction "JTAG_TMS_C11") (pintype "bidirectional"))
    )
    (net (code "131") (name "unconnected-(U2B-MMC1_CLK_U9-PadU9)") (class "Default")
      (node (ref "U2") (pin "U9") (pinfunction "MMC1_CLK_U9_U9") (pintype "bidirectional"))
    )
    (net (code "132") (name "unconnected-(U2B-MMC1_CMD_V9-PadV9)") (class "Default")
      (node (ref "U2") (pin "V9") (pinfunction "MMC1_CMD_V9_V9") (pintype "bidirectional"))
    )
    (net (code "133") (name "unconnected-(U2B-MMC1_DAT0_U7-PadU7)") (class "Default")
      (node (ref "U2") (pin "U7") (pinfunction "MMC1_DAT0_U7_U7") (pintype "bidirectional"))
    )
    (net (code "134") (name "unconnected-(U2B-MMC1_DAT1_V7-PadV7)") (class "Default")
      (node (ref "U2") (pin "V7") (pinfunction "MMC1_DAT1_V7_V7") (pintype "bidirectional"))
    )
    (net (code "135") (name "unconnected-(U2B-MMC1_DAT2_R8-PadR8)") (class "Default")
      (node (ref "U2") (pin "R8") (pinfunction "MMC1_DAT2_R8_R8") (pintype "bidirectional"))
    )
    (net (code "136") (name "unconnected-(U2B-MMC1_DAT3_T8-PadT8)") (class "Default")
      (node (ref "U2") (pin "T8") (pinfunction "MMC1_DAT3_T8_T8") (pintype "bidirectional"))
    )
    (net (code "137") (name "unconnected-(U2B-MMC1_DAT4_U8-PadU8)") (class "Default")
      (node (ref "U2") (pin "U8") (pinfunction "MMC1_DAT4_U8_U8") (pintype "bidirectional"))
    )
    (net (code "138") (name "unconnected-(U2B-MMC1_DAT5_V8-PadV8)") (class "Default")
      (node (ref "U2") (pin "V8") (pinfunction "MMC1_DAT5_V8_V8") (pintype "bidirectional"))
    )
    (net (code "139") (name "unconnected-(U2B-MMC1_DAT6_R9-PadR9)") (class "Default")
      (node (ref "U2") (pin "R9") (pinfunction "MMC1_DAT6_R9_R9") (pintype "bidirectional"))
    )
    (net (code "140") (name "unconnected-(U2B-MMC1_DAT7_T9-PadT9)") (class "Default")
      (node (ref "U2") (pin "T9") (pinfunction "MMC1_DAT7_T9_T9") (pintype "bidirectional"))
    )
    (net (code "141") (name "unconnected-(U2B-SPI1_CLK_A13-PadA13)") (class "Default")
      (node (ref "U2") (pin "A13") (pinfunction "SPI1_CLK_A13_A13") (pintype "bidirectional"))
    )
    (net (code "142") (name "unconnected-(U2B-SPI1_CS0_C12-PadC12)") (class "Default")
      (node (ref "U2") (pin "C12") (pinfunction "SPI1_CS0_C12_C12") (pintype "bidirectional"))
    )
    (net (code "143") (name "unconnected-(U2B-SPI1_D0_B13-PadB13)") (class "Default")
      (node (ref "U2") (pin "B13") (pinfunction "SPI1_D0_B13_B13") (pintype "bidirectional"))
    )
    (net (code "144") (name "unconnected-(U2B-SPI1_D1_D12-PadD12)") (class "Default")
      (node (ref "U2") (pin "D12") (pinfunction "SPI1_D1_D12_D12") (pintype "bidirectional"))
    )
    (net (code "145") (name "unconnected-(U2B-TIMER4_R7-PadR7)") (class "Default")
      (node (ref "U2") (pin "R7") (pinfunction "TIMER4_R7_R7") (pintype "bidirectional"))
    )
    (net (code "146") (name "unconnected-(U2B-TIMER5_T6-PadT6)") (class "Default")
      (node (ref "U2") (pin "T6") (pinfunction "TIMER5_T6_T6") (pintype "bidirectional"))
    )
    (net (code "147") (name "unconnected-(U2B-TIMER6_U6-PadU6)") (class "Default")
      (node (ref "U2") (pin "U6") (pinfunction "TIMER6_U6_U6") (pintype "bidirectional"))
    )
    (net (code "148") (name "unconnected-(U2B-TIMER7_T7-PadT7)") (class "Default")
      (node (ref "U2") (pin "T7") (pinfunction "TIMER7_T7_T7") (pintype "bidirectional"))
    )
    (net (code "149") (name "unconnected-(U2B-UART0_CTSN_E18-PadE18)") (class "Default")
      (node (ref "U2") (pin "E18") (pinfunction "UART0_CTSN_E18_E18") (pintype "bidirectional"))
    )
    (net (code "150") (name "unconnected-(U2B-UART0_RTSN_E17-PadE17)") (class "Default")
      (node (ref "U2") (pin "E17") (pinfunction "UART0_RTSN_E17_E17") (pintype "bidirectional"))
    )
    (net (code "151") (name "unconnected-(U2B-UART0_RXD_E15-PadE15)") (class "Default")
      (node (ref "U2") (pin "E15") (pinfunction "UART0_RXD_E15_E15") (pintype "bidirectional"))
    )
    (net (code "152") (name "unconnected-(U2B-UART0_TXD_E16-PadE16)") (class "Default")
      (node (ref "U2") (pin "E16") (pinfunction "UART0_TXD_E16_E16") (pintype "bidirectional"))
    )
    (net (code "153") (name "unconnected-(U2B-UART1_RXD_D16-PadD16)") (class "Default")
      (node (ref "U2") (pin "D16") (pinfunction "UART1_RXD_D16_D16") (pintype "bidirectional"))
    )
    (net (code "154") (name "unconnected-(U2B-UART1_TXD_D15-PadD15)") (class "Default")
      (node (ref "U2") (pin "D15") (pinfunction "UART1_TXD_D15_D15") (pintype "bidirectional"))
    )
    (net (code "155") (name "unconnected-(U2B-UART2_RXD_A17-PadA17)") (class "Default")
      (node (ref "U2") (pin "A17") (pinfunction "UART2_RXD_A17_A17") (pintype "bidirectional"))
    )
    (net (code "156") (name "unconnected-(U2B-UART2_TXD_B17-PadB17)") (class "Default")
      (node (ref "U2") (pin "B17") (pinfunction "UART2_TXD_B17_B17") (pintype "bidirectional"))
    )
    (net (code "157") (name "unconnected-(U2B-UART4_RXD_T17-PadT17)") (class "Default")
      (node (ref "U2") (pin "T17") (pinfunction "UART4_RXD_T17_T17") (pintype "bidirectional"))
    )
    (net (code "158") (name "unconnected-(U2B-UART4_TXD_U17-PadU17)") (class "Default")
      (node (ref "U2") (pin "U17") (pinfunction "UART4_TXD_U17_U17") (pintype "bidirectional"))
    )
    (net (code "159") (name "unconnected-(U2C-ADC_VREFP-PadB9)") (class "Default")
      (node (ref "U2") (pin "B9") (pinfunction "ADC_VREFP_B9") (pintype "bidirectional"))
    )
    (net (code "160") (name "unconnected-(U2C-AIN0-PadB6)") (class "Default")
      (node (ref "U2") (pin "B6") (pinfunction "AIN0_B6") (pintype "bidirectional"))
    )
    (net (code "161") (name "unconnected-(U2C-AIN1-PadC7)") (class "Default")
      (node (ref "U2") (pin "C7") (pinfunction "AIN1_C7") (pintype "bidirectional"))
    )
    (net (code "162") (name "unconnected-(U2C-AIN2-PadB7)") (class "Default")
      (node (ref "U2") (pin "B7") (pinfunction "AIN2_B7") (pintype "bidirectional"))
    )
    (net (code "163") (name "unconnected-(U2C-AIN3-PadA7)") (class "Default")
      (node (ref "U2") (pin "A7") (pinfunction "AIN3_A7") (pintype "bidirectional"))
    )
    (net (code "164") (name "unconnected-(U2C-AIN4-PadC8)") (class "Default")
      (node (ref "U2") (pin "C8") (pinfunction "AIN4_C8") (pintype "bidirectional"))
    )
    (net (code "165") (name "unconnected-(U2C-AIN5-PadB8)") (class "Default")
      (node (ref "U2") (pin "B8") (pinfunction "AIN5_B8") (pintype "bidirectional"))
    )
    (net (code "166") (name "unconnected-(U2C-AIN6-PadA8)") (class "Default")
      (node (ref "U2") (pin "A8") (pinfunction "AIN6_A8") (pintype "bidirectional"))
    )
    (net (code "167") (name "unconnected-(U2C-AIN7-PadC9)") (class "Default")
      (node (ref "U2") (pin "C9") (pinfunction "AIN7_C9") (pintype "bidirectional"))
    )
    (net (code "168") (name "unconnected-(U2C-HDMIDIS_GPIO1_27_V17-PadV17)") (class "Default")
      (node (ref "U2") (pin "V17") (pinfunction "HDMIDIS_GPIO1_27_V17_V17") (pintype "bidirectional"))
    )
    (net (code "169") (name "unconnected-(U2C-HDMIINT_GPIO1_25_U16-PadU16)") (class "Default")
      (node (ref "U2") (pin "U16") (pinfunction "HDMIINT_GPIO1_25_U16_U16") (pintype "bidirectional"))
    )
    (net (code "170") (name "unconnected-(U2C-LCD_DE_R6-PadR6)") (class "Default")
      (node (ref "U2") (pin "R6") (pinfunction "LCD_DE_R6_R6") (pintype "bidirectional"))
    )
    (net (code "171") (name "unconnected-(U2C-LCD_HSYNC_R5-PadR5)") (class "Default")
      (node (ref "U2") (pin "R5") (pinfunction "LCD_HSYNC_R5_R5") (pintype "bidirectional"))
    )
    (net (code "172") (name "unconnected-(U2C-LCD_PCLK_V5-PadV5)") (class "Default")
      (node (ref "U2") (pin "V5") (pinfunction "LCD_PCLK_V5_V5") (pintype "bidirectional"))
    )
    (net (code "173") (name "unconnected-(U2C-LCD_VSYNC_U5-PadU5)") (class "Default")
      (node (ref "U2") (pin "U5") (pinfunction "LCD_VSYNC_U5_U5") (pintype "bidirectional"))
    )
    (net (code "174") (name "unconnected-(U2C-USB0_CE-PadM15)") (class "Default")
      (node (ref "U2") (pin "M15") (pinfunction "USB0_CE_M15") (pintype "bidirectional"))
    )
    (net (code "175") (name "unconnected-(U2C-USB0_DRVVBUS-PadF16)") (class "Default")
      (node (ref "U2") (pin "F16") (pinfunction "USB0_DRVVBUS_F16") (pintype "bidirectional"))
    )
    (net (code "176") (name "unconnected-(U2C-USB1OC_GPIO1_26_T16-PadT16)") (class "Default")
      (node (ref "U2") (pin "T16") (pinfunction "USB1OC_GPIO1_26_T16_T16") (pintype "bidirectional"))
    )
    (net (code "177") (name "unconnected-(U2C-USB1_CE-PadP18)") (class "Default")
      (node (ref "U2") (pin "P18") (pinfunction "USB1_CE_P18") (pintype "bidirectional"))
    )
    (net (code "178") (name "unconnected-(U2C-USB1_DRVVBUS-PadF15)") (class "Default")
      (node (ref "U2") (pin "F15") (pinfunction "USB1_DRVVBUS_F15") (pintype "bidirectional"))
    )
    (net (code "179") (name "unconnected-(U2C-VOUT_ADC_1P8V_0-PadA4)") (class "Default")
      (node (ref "U2") (pin "A4") (pinfunction "VOUT_ADC_1P8V_0_A4") (pintype "bidirectional"))
    )
    (net (code "180") (name "unconnected-(U2C-VOUT_ADC_1P8V_1-PadA5)") (class "Default")
      (node (ref "U2") (pin "A5") (pinfunction "VOUT_ADC_1P8V_1_A5") (pintype "bidirectional"))
    )
    (net (code "181") (name "unconnected-(U2C-VSSA_ADC_0-PadA6)") (class "Default")
      (node (ref "U2") (pin "A6") (pinfunction "VSSA_ADC_0_A6") (pintype "bidirectional"))
    )
    (net (code "182") (name "unconnected-(U2C-VSSA_ADC_1-PadA9)") (class "Default")
      (node (ref "U2") (pin "A9") (pinfunction "VSSA_ADC_1_A9") (pintype "bidirectional"))
    )
    (net (code "183") (name "unconnected-(U2C-VSSA_ADC_2-PadE8)") (class "Default")
      (node (ref "U2") (pin "E8") (pinfunction "VSSA_ADC_2_E8") (pintype "bidirectional"))
    )
    (net (code "184") (name "unconnected-(U2E-CAP_VBB_MPU-PadC10)") (class "Default")
      (node (ref "U2") (pin "C10") (pinfunction "CAP_VBB_MPU_C10") (pintype "bidirectional"))
    )
    (net (code "185") (name "unconnected-(U2E-CAP_VDD_RTC-PadD6)") (class "Default")
      (node (ref "U2") (pin "D6") (pinfunction "CAP_VDD_RTC_D6") (pintype "bidirectional"))
    )
    (net (code "186") (name "unconnected-(U2E-CAP_VDD_SRAM_COR-PadD9)") (class "Default")
      (node (ref "U2") (pin "D9") (pinfunction "CAP_VDD_SRAM_COR_D9") (pintype "bidirectional"))
    )
    (net (code "187") (name "unconnected-(U2E-CAP_VDD_SRAM_MPU-PadD11)") (class "Default")
      (node (ref "U2") (pin "D11") (pinfunction "CAP_VDD_SRAM_MPU_D11") (pintype "bidirectional"))
    )
    (net (code "188") (name "unconnected-(U2E-TESTOUT-PadA3)") (class "Default")
      (node (ref "U2") (pin "A3") (pinfunction "TESTOUT_A3") (pintype "bidirectional"))
    )
    (net (code "189") (name "unconnected-(U2E-VDDA_ADC-PadD8)") (class "Default")
      (node (ref "U2") (pin "D8") (pinfunction "VDDA_ADC_D8") (pintype "bidirectional"))
    )
    (net (code "190") (name "unconnected-(U2E-VDDS_DDR1-PadE5)") (class "Default")
      (node (ref "U2") (pin "E5") (pinfunction "VDDS_DDR1_E5") (pintype "bidirectional"))
    )
    (net (code "191") (name "unconnected-(U2E-VDDS_DDR2-PadF5)") (class "Default")
      (node (ref "U2") (pin "F5") (pinfunction "VDDS_DDR2_F5") (pintype "bidirectional"))
    )
    (net (code "192") (name "unconnected-(U2E-VDDS_DDR3-PadG5)") (class "Default")
      (node (ref "U2") (pin "G5") (pinfunction "VDDS_DDR3_G5") (pintype "bidirectional"))
    )
    (net (code "193") (name "unconnected-(U2E-VDDS_DDR4-PadH5)") (class "Default")
      (node (ref "U2") (pin "H5") (pinfunction "VDDS_DDR4_H5") (pintype "bidirectional"))
    )
    (net (code "194") (name "unconnected-(U2E-VDDS_DDR5-PadJ5)") (class "Default")
      (node (ref "U2") (pin "J5") (pinfunction "VDDS_DDR5_J5") (pintype "bidirectional"))
    )
    (net (code "195") (name "unconnected-(U2E-VDDS_DDR6-PadK5)") (class "Default")
      (node (ref "U2") (pin "K5") (pinfunction "VDDS_DDR6_K5") (pintype "bidirectional"))
    )
    (net (code "196") (name "unconnected-(U2E-VDDS_DDR7-PadL5)") (class "Default")
      (node (ref "U2") (pin "L5") (pinfunction "VDDS_DDR7_L5") (pintype "bidirectional"))
    )
    (net (code "197") (name "unconnected-(U2E-VDD_3V3A1-PadE10)") (class "Default")
      (node (ref "U2") (pin "E10") (pinfunction "VDD_3V3A1_E10") (pintype "bidirectional"))
    )
    (net (code "198") (name "unconnected-(U2E-VDD_3V3A2-PadE11)") (class "Default")
      (node (ref "U2") (pin "E11") (pinfunction "VDD_3V3A2_E11") (pintype "bidirectional"))
    )
    (net (code "199") (name "unconnected-(U2E-VDD_3V3A3-PadE12)") (class "Default")
      (node (ref "U2") (pin "E12") (pinfunction "VDD_3V3A3_E12") (pintype "bidirectional"))
    )
    (net (code "200") (name "unconnected-(U2E-VDD_3V3A4-PadE13)") (class "Default")
      (node (ref "U2") (pin "E13") (pinfunction "VDD_3V3A4_E13") (pintype "bidirectional"))
    )
    (net (code "201") (name "unconnected-(U2E-VDD_3V3A5-PadF14)") (class "Default")
      (node (ref "U2") (pin "F14") (pinfunction "VDD_3V3A5_F14") (pintype "bidirectional"))
    )
    (net (code "202") (name "unconnected-(U2E-VDD_3V3A6-PadG14)") (class "Default")
      (node (ref "U2") (pin "G14") (pinfunction "VDD_3V3A6_G14") (pintype "bidirectional"))
    )
    (net (code "203") (name "unconnected-(U2E-VDD_3V3A7-PadH14)") (class "Default")
      (node (ref "U2") (pin "H14") (pinfunction "VDD_3V3A7_H14") (pintype "bidirectional"))
    )
    (net (code "204") (name "unconnected-(U2E-VDD_3V3A8-PadJ14)") (class "Default")
      (node (ref "U2") (pin "J14") (pinfunction "VDD_3V3A8_J14") (pintype "bidirectional"))
    )
    (net (code "205") (name "unconnected-(U2E-VDD_3V3A9-PadK14)") (class "Default")
      (node (ref "U2") (pin "K14") (pinfunction "VDD_3V3A9_K14") (pintype "bidirectional"))
    )
    (net (code "206") (name "unconnected-(U2E-VDD_3V3A10-PadL14)") (class "Default")
      (node (ref "U2") (pin "L14") (pinfunction "VDD_3V3A10_L14") (pintype "bidirectional"))
    )
    (net (code "207") (name "unconnected-(U2E-VDD_3V3A11-PadN5)") (class "Default")
      (node (ref "U2") (pin "N5") (pinfunction "VDD_3V3A11_N5") (pintype "bidirectional"))
    )
    (net (code "208") (name "unconnected-(U2E-VDD_3V3A12-PadN15)") (class "Default")
      (node (ref "U2") (pin "N15") (pinfunction "VDD_3V3A12_N15") (pintype "bidirectional"))
    )
    (net (code "209") (name "unconnected-(U2E-VDD_3V3A13-PadP5)") (class "Default")
      (node (ref "U2") (pin "P5") (pinfunction "VDD_3V3A13_P5") (pintype "bidirectional"))
    )
    (net (code "210") (name "unconnected-(U2E-VDD_3V3A14-PadP6)") (class "Default")
      (node (ref "U2") (pin "P6") (pinfunction "VDD_3V3A14_P6") (pintype "bidirectional"))
    )
    (net (code "211") (name "unconnected-(U2E-VDD_3V3A15-PadP7)") (class "Default")
      (node (ref "U2") (pin "P7") (pinfunction "VDD_3V3A15_P7") (pintype "bidirectional"))
    )
    (net (code "212") (name "unconnected-(U2E-VDD_3V3A16-PadP8)") (class "Default")
      (node (ref "U2") (pin "P8") (pinfunction "VDD_3V3A16_P8") (pintype "bidirectional"))
    )
    (net (code "213") (name "unconnected-(U2E-VDD_3V3A17-PadP10)") (class "Default")
      (node (ref "U2") (pin "P10") (pinfunction "VDD_3V3A17_P10") (pintype "bidirectional"))
    )
    (net (code "214") (name "unconnected-(U2E-VDD_3V3A18-PadP11)") (class "Default")
      (node (ref "U2") (pin "P11") (pinfunction "VDD_3V3A18_P11") (pintype "bidirectional"))
    )
    (net (code "215") (name "unconnected-(U2E-VDD_3V3A19-PadP12)") (class "Default")
      (node (ref "U2") (pin "P12") (pinfunction "VDD_3V3A19_P12") (pintype "bidirectional"))
    )
    (net (code "216") (name "unconnected-(U2E-VDD_3V3A20-PadP13)") (class "Default")
      (node (ref "U2") (pin "P13") (pinfunction "VDD_3V3A20_P13") (pintype "bidirectional"))
    )
    (net (code "217") (name "unconnected-(U2E-VDD_3V3A21-PadR15)") (class "Default")
      (node (ref "U2") (pin "R15") (pinfunction "VDD_3V3A21_R15") (pintype "bidirectional"))
    )
    (net (code "218") (name "unconnected-(U2E-VDD_CORE1-PadF6)") (class "Default")
      (node (ref "U2") (pin "F6") (pinfunction "VDD_CORE1_F6") (pintype "bidirectional"))
    )
    (net (code "219") (name "unconnected-(U2E-VDD_CORE2-PadF7)") (class "Default")
      (node (ref "U2") (pin "F7") (pinfunction "VDD_CORE2_F7") (pintype "bidirectional"))
    )
    (net (code "220") (name "unconnected-(U2E-VDD_CORE3-PadG6)") (class "Default")
      (node (ref "U2") (pin "G6") (pinfunction "VDD_CORE3_G6") (pintype "bidirectional"))
    )
    (net (code "221") (name "unconnected-(U2E-VDD_CORE4-PadG7)") (class "Default")
      (node (ref "U2") (pin "G7") (pinfunction "VDD_CORE4_G7") (pintype "bidirectional"))
    )
    (net (code "222") (name "unconnected-(U2E-VDD_CORE5-PadG10)") (class "Default")
      (node (ref "U2") (pin "G10") (pinfunction "VDD_CORE5_G10") (pintype "bidirectional"))
    )
    (net (code "223") (name "unconnected-(U2E-VDD_CORE6-PadH11)") (class "Default")
      (node (ref "U2") (pin "H11") (pinfunction "VDD_CORE6_H11") (pintype "bidirectional"))
    )
    (net (code "224") (name "unconnected-(U2E-VDD_CORE7-PadJ12)") (class "Default")
      (node (ref "U2") (pin "J12") (pinfunction "VDD_CORE7_J12") (pintype "bidirectional"))
    )
    (net (code "225") (name "unconnected-(U2E-VDD_CORE8-PadK6)") (class "Default")
      (node (ref "U2") (pin "K6") (pinfunction "VDD_CORE8_K6") (pintype "bidirectional"))
    )
    (net (code "226") (name "unconnected-(U2E-VDD_CORE9-PadK8)") (class "Default")
      (node (ref "U2") (pin "K8") (pinfunction "VDD_CORE9_K8") (pintype "bidirectional"))
    )
    (net (code "227") (name "unconnected-(U2E-VDD_CORE10-PadK12)") (class "Default")
      (node (ref "U2") (pin "K12") (pinfunction "VDD_CORE10_K12") (pintype "bidirectional"))
    )
    (net (code "228") (name "unconnected-(U2E-VDD_CORE11-PadL6)") (class "Default")
      (node (ref "U2") (pin "L6") (pinfunction "VDD_CORE11_L6") (pintype "bidirectional"))
    )
    (net (code "229") (name "unconnected-(U2E-VDD_CORE12-PadL7)") (class "Default")
      (node (ref "U2") (pin "L7") (pinfunction "VDD_CORE12_L7") (pintype "bidirectional"))
    )
    (net (code "230") (name "unconnected-(U2E-VDD_CORE13-PadL8)") (class "Default")
      (node (ref "U2") (pin "L8") (pinfunction "VDD_CORE13_L8") (pintype "bidirectional"))
    )
    (net (code "231") (name "unconnected-(U2E-VDD_CORE14-PadL9)") (class "Default")
      (node (ref "U2") (pin "L9") (pinfunction "VDD_CORE14_L9") (pintype "bidirectional"))
    )
    (net (code "232") (name "unconnected-(U2E-VDD_CORE15-PadM11)") (class "Default")
      (node (ref "U2") (pin "M11") (pinfunction "VDD_CORE15_M11") (pintype "bidirectional"))
    )
    (net (code "233") (name "unconnected-(U2E-VDD_CORE16-PadM13)") (class "Default")
      (node (ref "U2") (pin "M13") (pinfunction "VDD_CORE16_M13") (pintype "bidirectional"))
    )
    (net (code "234") (name "unconnected-(U2E-VDD_CORE17-PadN8)") (class "Default")
      (node (ref "U2") (pin "N8") (pinfunction "VDD_CORE17_N8") (pintype "bidirectional"))
    )
    (net (code "235") (name "unconnected-(U2E-VDD_CORE18-PadN9)") (class "Default")
      (node (ref "U2") (pin "N9") (pinfunction "VDD_CORE18_N9") (pintype "bidirectional"))
    )
    (net (code "236") (name "unconnected-(U2E-VDD_CORE19-PadN12)") (class "Default")
      (node (ref "U2") (pin "N12") (pinfunction "VDD_CORE19_N12") (pintype "bidirectional"))
    )
    (net (code "237") (name "unconnected-(U2E-VDD_CORE20-PadN13)") (class "Default")
      (node (ref "U2") (pin "N13") (pinfunction "VDD_CORE20_N13") (pintype "bidirectional"))
    )
    (net (code "238") (name "unconnected-(U2E-VDD_MPU0-PadF10)") (class "Default")
      (node (ref "U2") (pin "F10") (pinfunction "VDD_MPU0_F10") (pintype "bidirectional"))
    )
    (net (code "239") (name "unconnected-(U2E-VDD_MPU1-PadF11)") (class "Default")
      (node (ref "U2") (pin "F11") (pinfunction "VDD_MPU1_F11") (pintype "bidirectional"))
    )
    (net (code "240") (name "unconnected-(U2E-VDD_MPU2-PadF12)") (class "Default")
      (node (ref "U2") (pin "F12") (pinfunction "VDD_MPU2_F12") (pintype "bidirectional"))
    )
    (net (code "241") (name "unconnected-(U2E-VDD_MPU3-PadF13)") (class "Default")
      (node (ref "U2") (pin "F13") (pinfunction "VDD_MPU3_F13") (pintype "bidirectional"))
    )
    (net (code "242") (name "unconnected-(U2E-VDD_MPU4-PadG13)") (class "Default")
      (node (ref "U2") (pin "G13") (pinfunction "VDD_MPU4_G13") (pintype "bidirectional"))
    )
    (net (code "243") (name "unconnected-(U2E-VDD_MPU5-PadH13)") (class "Default")
      (node (ref "U2") (pin "H13") (pinfunction "VDD_MPU5_H13") (pintype "bidirectional"))
    )
    (net (code "244") (name "unconnected-(U2E-VDD_MPU6-PadJ13)") (class "Default")
      (node (ref "U2") (pin "J13") (pinfunction "VDD_MPU6_J13") (pintype "bidirectional"))
    )
    (net (code "245") (name "unconnected-(U2E-VDD_MPU_MON-PadA2)") (class "Default")
      (node (ref "U2") (pin "A2") (pinfunction "VDD_MPU_MON_A2") (pintype "bidirectional"))
    )
    (net (code "246") (name "unconnected-(U2E-VDD_PLL1-PadE7)") (class "Default")
      (node (ref "U2") (pin "E7") (pinfunction "VDD_PLL1_E7") (pintype "bidirectional"))
    )
    (net (code "247") (name "unconnected-(U2E-VDD_PLL2-PadH15)") (class "Default")
      (node (ref "U2") (pin "H15") (pinfunction "VDD_PLL2_H15") (pintype "bidirectional"))
    )
    (net (code "248") (name "unconnected-(U2E-VDD_PLL3-PadR10)") (class "Default")
      (node (ref "U2") (pin "R10") (pinfunction "VDD_PLL3_R10") (pintype "bidirectional"))
    )
    (net (code "249") (name "unconnected-(U2E-VDD_PLL4-PadR11)") (class "Default")
      (node (ref "U2") (pin "R11") (pinfunction "VDD_PLL4_R11") (pintype "bidirectional"))
    )
    (net (code "250") (name "unconnected-(U2E-VDD_RTC1-PadD7)") (class "Default")
      (node (ref "U2") (pin "D7") (pinfunction "VDD_RTC1_D7") (pintype "bidirectional"))
    )
    (net (code "251") (name "unconnected-(U2E-VDD_RTC2-PadE6)") (class "Default")
      (node (ref "U2") (pin "E6") (pinfunction "VDD_RTC2_E6") (pintype "bidirectional"))
    )
    (net (code "252") (name "unconnected-(U2E-VDD_RTC4-PadF9)") (class "Default")
      (node (ref "U2") (pin "F9") (pinfunction "VDD_RTC4_F9") (pintype "bidirectional"))
    )
    (net (code "253") (name "unconnected-(U2E-VDD_RTC5-PadK13)") (class "Default")
      (node (ref "U2") (pin "K13") (pinfunction "VDD_RTC5_K13") (pintype "bidirectional"))
    )
    (net (code "254") (name "unconnected-(U2E-VDD_RTC6-PadN6)") (class "Default")
      (node (ref "U2") (pin "N6") (pinfunction "VDD_RTC6_N6") (pintype "bidirectional"))
    )
    (net (code "255") (name "unconnected-(U2E-VDD_RTC7-PadP9)") (class "Default")
      (node (ref "U2") (pin "P9") (pinfunction "VDD_RTC7_P9") (pintype "bidirectional"))
    )
    (net (code "256") (name "unconnected-(U2E-VDD_RTC8-PadP14)") (class "Default")
      (node (ref "U2") (pin "P14") (pinfunction "VDD_RTC8_P14") (pintype "bidirectional"))
    )
    (net (code "257") (name "unconnected-(U2E-VPP-PadM5)") (class "Default")
      (node (ref "U2") (pin "M5") (pinfunction "VPP_M5") (pintype "bidirectional"))
    )
    (net (code "258") (name "unconnected-(U2F-DGND2-PadA18)") (class "Default")
      (node (ref "U2") (pin "A18") (pinfunction "DGND2_A18") (pintype "bidirectional"))
    )
    (net (code "259") (name "unconnected-(U2F-DGND3-PadE19)") (class "Default")
      (node (ref "U2") (pin "E19") (pinfunction "DGND3_E19") (pintype "bidirectional"))
    )
    (net (code "260") (name "unconnected-(U2F-DGND4-PadE20)") (class "Default")
      (node (ref "U2") (pin "E20") (pinfunction "DGND4_E20") (pintype "bidirectional"))
    )
    (net (code "261") (name "unconnected-(U2F-DGND5-PadF8)") (class "Default")
      (node (ref "U2") (pin "F8") (pinfunction "DGND5_F8") (pintype "bidirectional"))
    )
    (net (code "262") (name "unconnected-(U2F-DGND6-PadF19)") (class "Default")
      (node (ref "U2") (pin "F19") (pinfunction "DGND6_F19") (pintype "bidirectional"))
    )
    (net (code "263") (name "unconnected-(U2F-DGND7-PadG8)") (class "Default")
      (node (ref "U2") (pin "G8") (pinfunction "DGND7_G8") (pintype "bidirectional"))
    )
    (net (code "264") (name "unconnected-(U2F-DGND8-PadG9)") (class "Default")
      (node (ref "U2") (pin "G9") (pinfunction "DGND8_G9") (pintype "bidirectional"))
    )
    (net (code "265") (name "unconnected-(U2F-DGND9-PadG11)") (class "Default")
      (node (ref "U2") (pin "G11") (pinfunction "DGND9_G11") (pintype "bidirectional"))
    )
    (net (code "266") (name "unconnected-(U2F-DGND10-PadG12)") (class "Default")
      (node (ref "U2") (pin "G12") (pinfunction "DGND10_G12") (pintype "bidirectional"))
    )
    (net (code "267") (name "unconnected-(U2F-DGND11-PadG19)") (class "Default")
      (node (ref "U2") (pin "G19") (pinfunction "DGND11_G19") (pintype "bidirectional"))
    )
    (net (code "268") (name "unconnected-(U2F-DGND12-PadH6)") (class "Default")
      (node (ref "U2") (pin "H6") (pinfunction "DGND12_H6") (pintype "bidirectional"))
    )
    (net (code "269") (name "unconnected-(U2F-DGND13-PadH7)") (class "Default")
      (node (ref "U2") (pin "H7") (pinfunction "DGND13_H7") (pintype "bidirectional"))
    )
    (net (code "270") (name "unconnected-(U2F-DGND14-PadH8)") (class "Default")
      (node (ref "U2") (pin "H8") (pinfunction "DGND14_H8") (pintype "bidirectional"))
    )
    (net (code "271") (name "unconnected-(U2F-DGND15-PadH9)") (class "Default")
      (node (ref "U2") (pin "H9") (pinfunction "DGND15_H9") (pintype "bidirectional"))
    )
    (net (code "272") (name "unconnected-(U2F-DGND16-PadH10)") (class "Default")
      (node (ref "U2") (pin "H10") (pinfunction "DGND16_H10") (pintype "bidirectional"))
    )
    (net (code "273") (name "unconnected-(U2F-DGND17-PadH12)") (class "Default")
      (node (ref "U2") (pin "H12") (pinfunction "DGND17_H12") (pintype "bidirectional"))
    )
    (net (code "274") (name "unconnected-(U2F-DGND18-PadH19)") (class "Default")
      (node (ref "U2") (pin "H19") (pinfunction "DGND18_H19") (pintype "bidirectional"))
    )
    (net (code "275") (name "unconnected-(U2F-DGND20-PadJ7)") (class "Default")
      (node (ref "U2") (pin "J7") (pinfunction "DGND20_J7") (pintype "bidirectional"))
    )
    (net (code "276") (name "unconnected-(U2F-DGND21-PadJ8)") (class "Default")
      (node (ref "U2") (pin "J8") (pinfunction "DGND21_J8") (pintype "bidirectional"))
    )
    (net (code "277") (name "unconnected-(U2F-DGND22-PadJ9)") (class "Default")
      (node (ref "U2") (pin "J9") (pinfunction "DGND22_J9") (pintype "bidirectional"))
    )
    (net (code "278") (name "unconnected-(U2F-DGND23-PadJ10)") (class "Default")
      (node (ref "U2") (pin "J10") (pinfunction "DGND23_J10") (pintype "bidirectional"))
    )
    (net (code "279") (name "unconnected-(U2F-DGND24-PadJ11)") (class "Default")
      (node (ref "U2") (pin "J11") (pinfunction "DGND24_J11") (pintype "bidirectional"))
    )
    (net (code "280") (name "unconnected-(U2F-DGND25-PadJ19)") (class "Default")
      (node (ref "U2") (pin "J19") (pinfunction "DGND25_J19") (pintype "bidirectional"))
    )
    (net (code "281") (name "unconnected-(U2F-DGND26-PadJ20)") (class "Default")
      (node (ref "U2") (pin "J20") (pinfunction "DGND26_J20") (pintype "bidirectional"))
    )
    (net (code "282") (name "unconnected-(U2F-DGND27-PadK7)") (class "Default")
      (node (ref "U2") (pin "K7") (pinfunction "DGND27_K7") (pintype "bidirectional"))
    )
    (net (code "283") (name "unconnected-(U2F-DGND28-PadK9)") (class "Default")
      (node (ref "U2") (pin "K9") (pinfunction "DGND28_K9") (pintype "bidirectional"))
    )
    (net (code "284") (name "unconnected-(U2F-DGND29-PadK10)") (class "Default")
      (node (ref "U2") (pin "K10") (pinfunction "DGND29_K10") (pintype "bidirectional"))
    )
    (net (code "285") (name "unconnected-(U2F-DGND30-PadK11)") (class "Default")
      (node (ref "U2") (pin "K11") (pinfunction "DGND30_K11") (pintype "bidirectional"))
    )
    (net (code "286") (name "unconnected-(U2F-DGND31-PadK19)") (class "Default")
      (node (ref "U2") (pin "K19") (pinfunction "DGND31_K19") (pintype "bidirectional"))
    )
    (net (code "287") (name "unconnected-(U2F-DGND32-PadL10)") (class "Default")
      (node (ref "U2") (pin "L10") (pinfunction "DGND32_L10") (pintype "bidirectional"))
    )
    (net (code "288") (name "unconnected-(U2F-DGND33-PadL11)") (class "Default")
      (node (ref "U2") (pin "L11") (pinfunction "DGND33_L11") (pintype "bidirectional"))
    )
    (net (code "289") (name "unconnected-(U2F-DGND34-PadL12)") (class "Default")
      (node (ref "U2") (pin "L12") (pinfunction "DGND34_L12") (pintype "bidirectional"))
    )
    (net (code "290") (name "unconnected-(U2F-DGND35-PadL13)") (class "Default")
      (node (ref "U2") (pin "L13") (pinfunction "DGND35_L13") (pintype "bidirectional"))
    )
    (net (code "291") (name "unconnected-(U2F-DGND38-PadM6)") (class "Default")
      (node (ref "U2") (pin "M6") (pinfunction "DGND38_M6") (pintype "bidirectional"))
    )
    (net (code "292") (name "unconnected-(U2F-DGND39-PadM7)") (class "Default")
      (node (ref "U2") (pin "M7") (pinfunction "DGND39_M7") (pintype "bidirectional"))
    )
    (net (code "293") (name "unconnected-(U2F-DGND40-PadM8)") (class "Default")
      (node (ref "U2") (pin "M8") (pinfunction "DGND40_M8") (pintype "bidirectional"))
    )
    (net (code "294") (name "unconnected-(U2F-DGND41-PadM9)") (class "Default")
      (node (ref "U2") (pin "M9") (pinfunction "DGND41_M9") (pintype "bidirectional"))
    )
    (net (code "295") (name "unconnected-(U2F-DGND43-PadM12)") (class "Default")
      (node (ref "U2") (pin "M12") (pinfunction "DGND43_M12") (pintype "bidirectional"))
    )
    (net (code "296") (name "unconnected-(U2F-DGND44-PadM14)") (class "Default")
      (node (ref "U2") (pin "M14") (pinfunction "DGND44_M14") (pintype "bidirectional"))
    )
    (net (code "297") (name "unconnected-(U2F-DGND47-PadN10)") (class "Default")
      (node (ref "U2") (pin "N10") (pinfunction "DGND47_N10") (pintype "bidirectional"))
    )
    (net (code "298") (name "unconnected-(U2F-DGND48-PadN11)") (class "Default")
      (node (ref "U2") (pin "N11") (pinfunction "DGND48_N11") (pintype "bidirectional"))
    )
    (net (code "299") (name "unconnected-(U2F-DGND49-PadN14)") (class "Default")
      (node (ref "U2") (pin "N14") (pinfunction "DGND49_N14") (pintype "bidirectional"))
    )
    (net (code "300") (name "unconnected-(U2F-DGND50-PadN19)") (class "Default")
      (node (ref "U2") (pin "N19") (pinfunction "DGND50_N19") (pintype "bidirectional"))
    )
    (net (code "301") (name "unconnected-(U2F-DGND51-PadN20)") (class "Default")
      (node (ref "U2") (pin "N20") (pinfunction "DGND51_N20") (pintype "bidirectional"))
    )
    (net (code "302") (name "unconnected-(U2F-DGND52-PadP19)") (class "Default")
      (node (ref "U2") (pin "P19") (pinfunction "DGND52_P19") (pintype "bidirectional"))
    )
    (net (code "303") (name "unconnected-(U2F-DGND53-PadP20)") (class "Default")
      (node (ref "U2") (pin "P20") (pinfunction "DGND53_P20") (pintype "bidirectional"))
    )
    (net (code "304") (name "unconnected-(U2F-DGND54-PadR19)") (class "Default")
      (node (ref "U2") (pin "R19") (pinfunction "DGND54_R19") (pintype "bidirectional"))
    )
    (net (code "305") (name "unconnected-(U2F-DGND55-PadR20)") (class "Default")
      (node (ref "U2") (pin "R20") (pinfunction "DGND55_R20") (pintype "bidirectional"))
    )
    (net (code "306") (name "unconnected-(U2F-DGND56-PadT19)") (class "Default")
      (node (ref "U2") (pin "T19") (pinfunction "DGND56_T19") (pintype "bidirectional"))
    )
    (net (code "307") (name "unconnected-(U2F-DGND57-PadT20)") (class "Default")
      (node (ref "U2") (pin "T20") (pinfunction "DGND57_T20") (pintype "bidirectional"))
    )
    (net (code "308") (name "unconnected-(U2F-DGND58-PadU19)") (class "Default")
      (node (ref "U2") (pin "U19") (pinfunction "DGND58_U19") (pintype "bidirectional"))
    )
    (net (code "309") (name "unconnected-(U2F-DGND60-PadV18)") (class "Default")
      (node (ref "U2") (pin "V18") (pinfunction "DGND60_V18") (pintype "bidirectional"))
    )
    (net (code "310") (name "unconnected-(U2F-DGND63-PadW3)") (class "Default")
      (node (ref "U2") (pin "W3") (pinfunction "DGND63_W3") (pintype "bidirectional"))
    )
    (net (code "311") (name "unconnected-(U2F-DGND65-PadW5)") (class "Default")
      (node (ref "U2") (pin "W5") (pinfunction "DGND65_W5") (pintype "bidirectional"))
    )
    (net (code "312") (name "unconnected-(U2F-DGND66-PadW6)") (class "Default")
      (node (ref "U2") (pin "W6") (pinfunction "DGND66_W6") (pintype "bidirectional"))
    )
    (net (code "313") (name "unconnected-(U2F-DGND67-PadW7)") (class "Default")
      (node (ref "U2") (pin "W7") (pinfunction "DGND67_W7") (pintype "bidirectional"))
    )
    (net (code "314") (name "unconnected-(U2F-DGND68-PadW8)") (class "Default")
      (node (ref "U2") (pin "W8") (pinfunction "DGND68_W8") (pintype "bidirectional"))
    )
    (net (code "315") (name "unconnected-(U2F-DGND69-PadW9)") (class "Default")
      (node (ref "U2") (pin "W9") (pinfunction "DGND69_W9") (pintype "bidirectional"))
    )
    (net (code "316") (name "unconnected-(U2F-DGND70-PadW10)") (class "Default")
      (node (ref "U2") (pin "W10") (pinfunction "DGND70_W10") (pintype "bidirectional"))
    )
    (net (code "317") (name "unconnected-(U2F-DGND72-PadW12)") (class "Default")
      (node (ref "U2") (pin "W12") (pinfunction "DGND72_W12") (pintype "bidirectional"))
    )
    (net (code "318") (name "unconnected-(U2F-DGND73-PadW13)") (class "Default")
      (node (ref "U2") (pin "W13") (pinfunction "DGND73_W13") (pintype "bidirectional"))
    )
    (net (code "319") (name "unconnected-(U2F-DGND74-PadW14)") (class "Default")
      (node (ref "U2") (pin "W14") (pinfunction "DGND74_W14") (pintype "bidirectional"))
    )
    (net (code "320") (name "unconnected-(U2F-DGND75-PadW15)") (class "Default")
      (node (ref "U2") (pin "W15") (pinfunction "DGND75_W15") (pintype "bidirectional"))
    )
    (net (code "321") (name "unconnected-(U2F-DGND76-PadW16)") (class "Default")
      (node (ref "U2") (pin "W16") (pinfunction "DGND76_W16") (pintype "bidirectional"))
    )
    (net (code "322") (name "unconnected-(U2F-DGND77-PadW17)") (class "Default")
      (node (ref "U2") (pin "W17") (pinfunction "DGND77_W17") (pintype "bidirectional"))
    )
    (net (code "323") (name "unconnected-(U2F-DGND78-PadW18)") (class "Default")
      (node (ref "U2") (pin "W18") (pinfunction "DGND78_W18") (pintype "bidirectional"))
    )
    (net (code "324") (name "unconnected-(U2F-DGND79-PadW19)") (class "Default")
      (node (ref "U2") (pin "W19") (pinfunction "DGND79_W19") (pintype "bidirectional"))
    )
    (net (code "325") (name "unconnected-(U2F-DGND82-PadY7)") (class "Default")
      (node (ref "U2") (pin "Y7") (pinfunction "DGND82_Y7") (pintype "bidirectional"))
    )
    (net (code "326") (name "unconnected-(U2F-DGND83-PadY10)") (class "Default")
      (node (ref "U2") (pin "Y10") (pinfunction "DGND83_Y10") (pintype "bidirectional"))
    )
    (net (code "327") (name "unconnected-(U2F-DGND84-PadY12)") (class "Default")
      (node (ref "U2") (pin "Y12") (pinfunction "DGND84_Y12") (pintype "bidirectional"))
    )
    (net (code "328") (name "unconnected-(U2F-DGND85-PadY15)") (class "Default")
      (node (ref "U2") (pin "Y15") (pinfunction "DGND85_Y15") (pintype "bidirectional"))
    )
    (net (code "329") (name "unconnected-(U3-NC-Pad1)") (class "Default")
      (node (ref "U3") (pin "1") (pinfunction "NC_1") (pintype "passive"))
    )
  )
)
